# NEW_LINE_EN.net
KiCad netlist of a schematic drawn in EAGLE
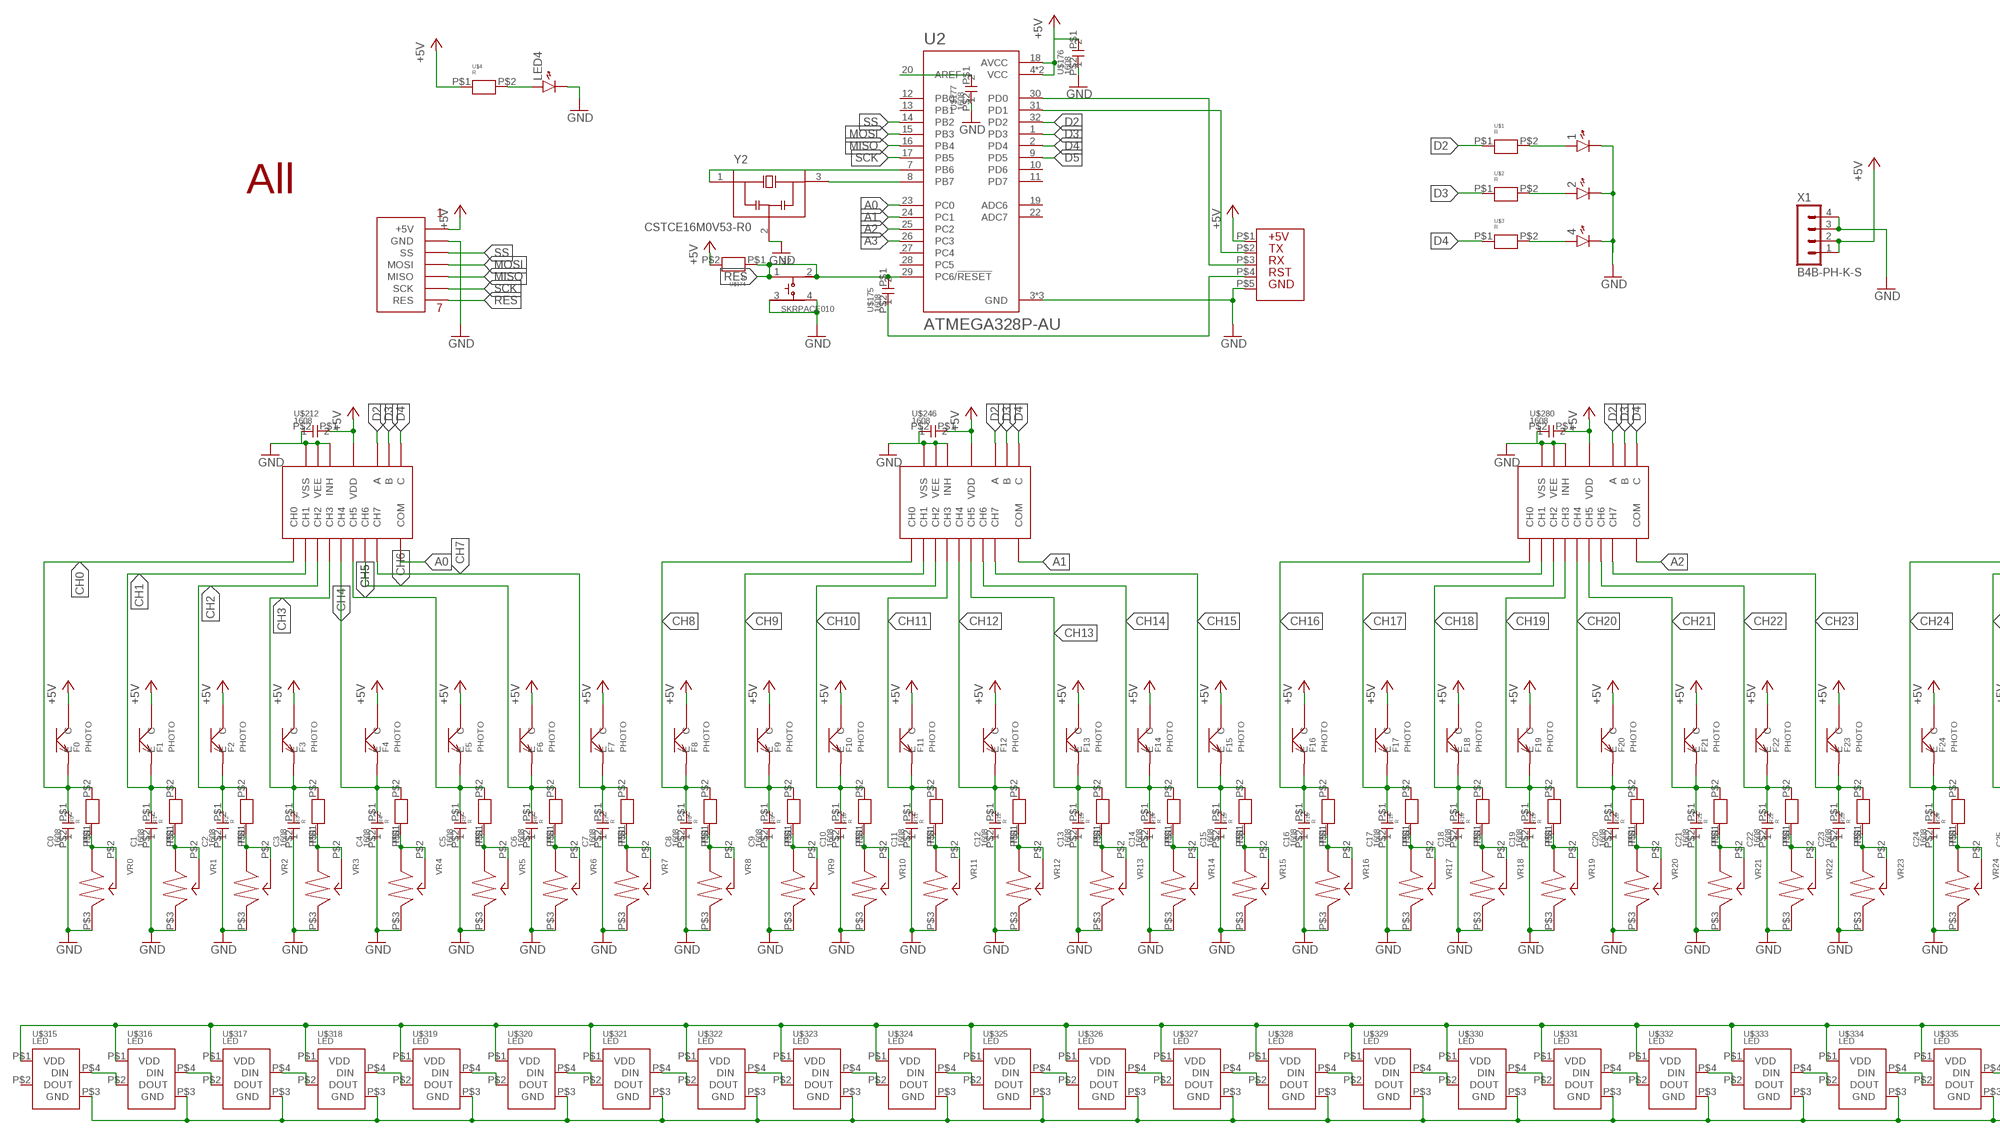
[diagram p0: schematic, sheet 1, part 1 of 2]
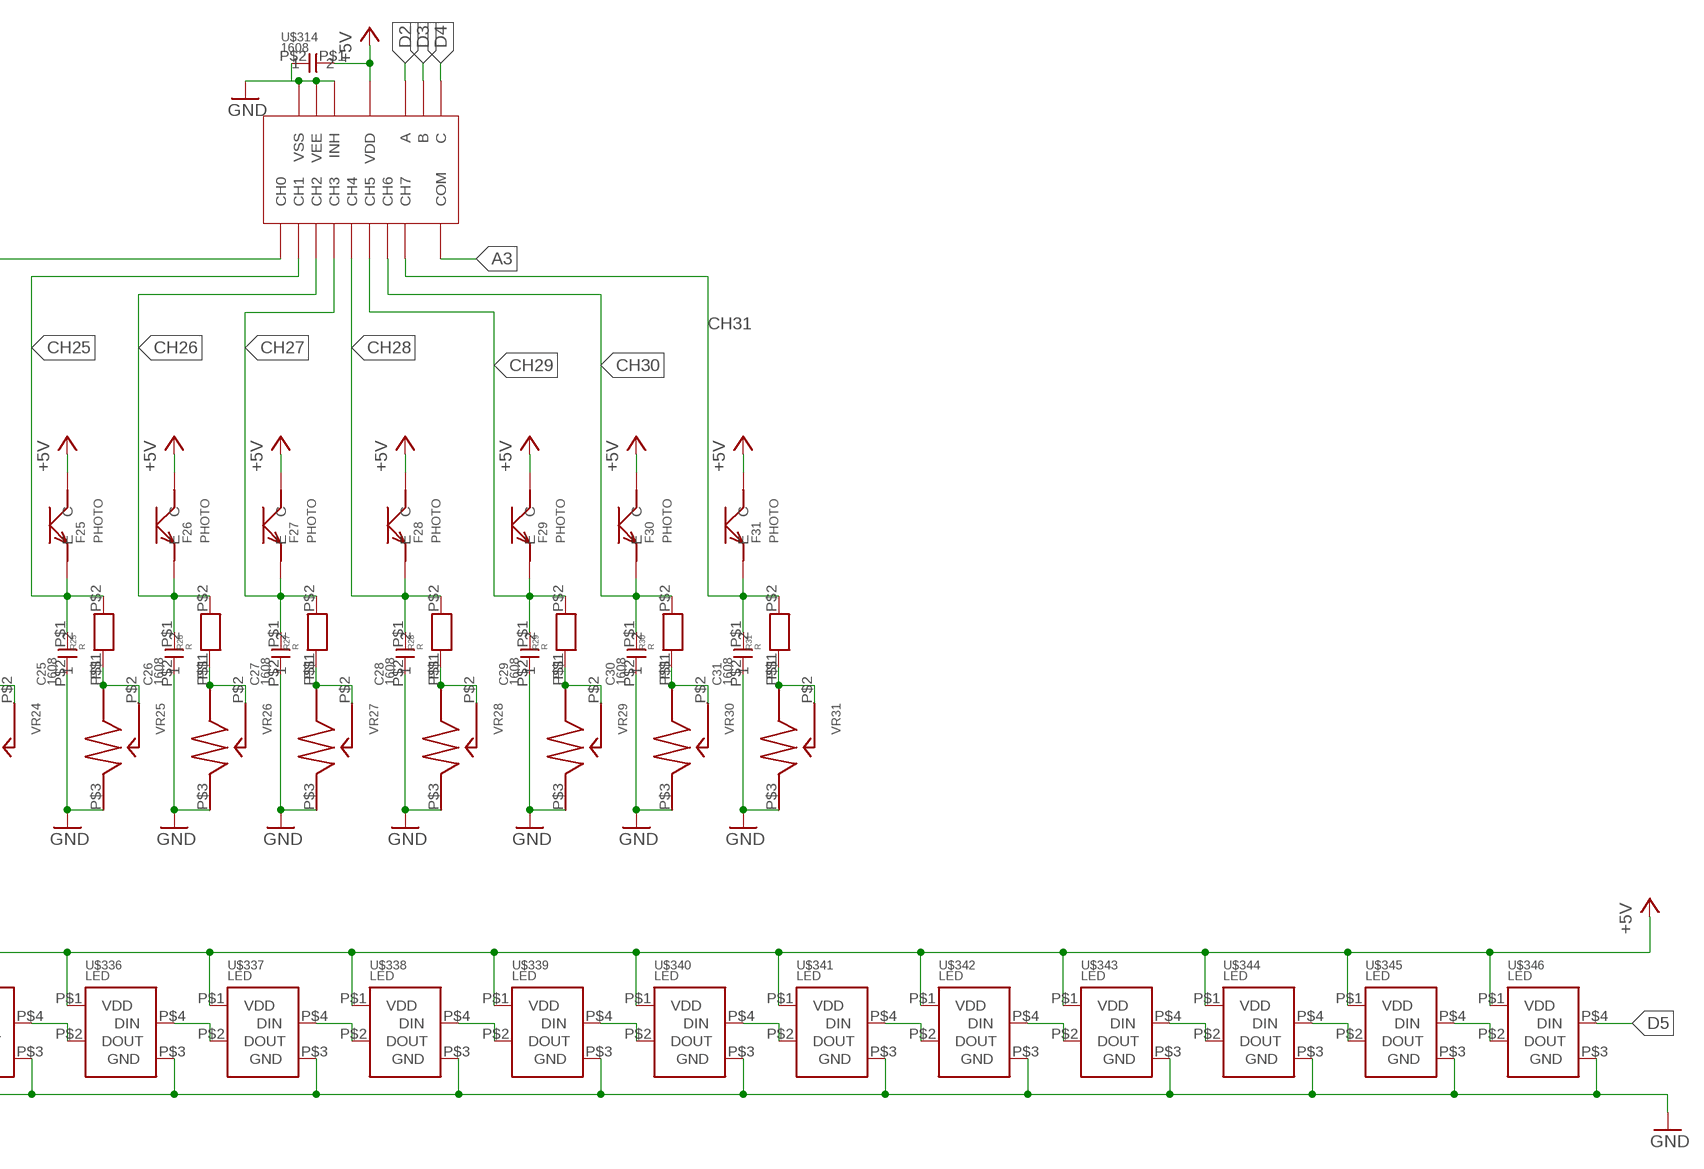
[diagram p1: schematic, sheet 1, part 2 of 2]

(export (version "E")
  (design (tool "Eeschema 10.0.6"))
  (components
    (comp (ref "1")
      (value "LED1608")
      (footprint "eagle-import:LED1608")
      (libsource (lib "eagle-import") (part "LED1608"))
    )
    (comp (ref "2")
      (value "LED1608")
      (footprint "eagle-import:LED1608")
      (libsource (lib "eagle-import") (part "LED1608"))
    )
    (comp (ref "4")
      (value "LED1608")
      (footprint "eagle-import:LED1608")
      (libsource (lib "eagle-import") (part "LED1608"))
    )
    (comp (ref "C0")
      (value "1608")
      (footprint "eagle-import:CON")
      (libsource (lib "eagle-import") (part "1608"))
    )
    (comp (ref "C1")
      (value "1608")
      (footprint "eagle-import:CON")
      (libsource (lib "eagle-import") (part "1608"))
    )
    (comp (ref "C2")
      (value "1608")
      (footprint "eagle-import:CON")
      (libsource (lib "eagle-import") (part "1608"))
    )
    (comp (ref "C3")
      (value "1608")
      (footprint "eagle-import:CON")
      (libsource (lib "eagle-import") (part "1608"))
    )
    (comp (ref "C4")
      (value "1608")
      (footprint "eagle-import:CON")
      (libsource (lib "eagle-import") (part "1608"))
    )
    (comp (ref "C5")
      (value "1608")
      (footprint "eagle-import:CON")
      (libsource (lib "eagle-import") (part "1608"))
    )
    (comp (ref "C6")
      (value "1608")
      (footprint "eagle-import:CON")
      (libsource (lib "eagle-import") (part "1608"))
    )
    (comp (ref "C7")
      (value "1608")
      (footprint "eagle-import:CON")
      (libsource (lib "eagle-import") (part "1608"))
    )
    (comp (ref "C8")
      (value "1608")
      (footprint "eagle-import:CON")
      (libsource (lib "eagle-import") (part "1608"))
    )
    (comp (ref "C9")
      (value "1608")
      (footprint "eagle-import:CON")
      (libsource (lib "eagle-import") (part "1608"))
    )
    (comp (ref "C10")
      (value "1608")
      (footprint "eagle-import:CON")
      (libsource (lib "eagle-import") (part "1608"))
    )
    (comp (ref "C11")
      (value "1608")
      (footprint "eagle-import:CON")
      (libsource (lib "eagle-import") (part "1608"))
    )
    (comp (ref "C12")
      (value "1608")
      (footprint "eagle-import:CON")
      (libsource (lib "eagle-import") (part "1608"))
    )
    (comp (ref "C13")
      (value "1608")
      (footprint "eagle-import:CON")
      (libsource (lib "eagle-import") (part "1608"))
    )
    (comp (ref "C14")
      (value "1608")
      (footprint "eagle-import:CON")
      (libsource (lib "eagle-import") (part "1608"))
    )
    (comp (ref "C15")
      (value "1608")
      (footprint "eagle-import:CON")
      (libsource (lib "eagle-import") (part "1608"))
    )
    (comp (ref "C16")
      (value "1608")
      (footprint "eagle-import:CON")
      (libsource (lib "eagle-import") (part "1608"))
    )
    (comp (ref "C17")
      (value "1608")
      (footprint "eagle-import:CON")
      (libsource (lib "eagle-import") (part "1608"))
    )
    (comp (ref "C18")
      (value "1608")
      (footprint "eagle-import:CON")
      (libsource (lib "eagle-import") (part "1608"))
    )
    (comp (ref "C19")
      (value "1608")
      (footprint "eagle-import:CON")
      (libsource (lib "eagle-import") (part "1608"))
    )
    (comp (ref "C20")
      (value "1608")
      (footprint "eagle-import:CON")
      (libsource (lib "eagle-import") (part "1608"))
    )
    (comp (ref "C21")
      (value "1608")
      (footprint "eagle-import:CON")
      (libsource (lib "eagle-import") (part "1608"))
    )
    (comp (ref "C22")
      (value "1608")
      (footprint "eagle-import:CON")
      (libsource (lib "eagle-import") (part "1608"))
    )
    (comp (ref "C23")
      (value "1608")
      (footprint "eagle-import:CON")
      (libsource (lib "eagle-import") (part "1608"))
    )
    (comp (ref "C24")
      (value "1608")
      (footprint "eagle-import:CON")
      (libsource (lib "eagle-import") (part "1608"))
    )
    (comp (ref "C25")
      (value "1608")
      (footprint "eagle-import:CON")
      (libsource (lib "eagle-import") (part "1608"))
    )
    (comp (ref "C26")
      (value "1608")
      (footprint "eagle-import:CON")
      (libsource (lib "eagle-import") (part "1608"))
    )
    (comp (ref "C27")
      (value "1608")
      (footprint "eagle-import:CON")
      (libsource (lib "eagle-import") (part "1608"))
    )
    (comp (ref "C28")
      (value "1608")
      (footprint "eagle-import:CON")
      (libsource (lib "eagle-import") (part "1608"))
    )
    (comp (ref "C29")
      (value "1608")
      (footprint "eagle-import:CON")
      (libsource (lib "eagle-import") (part "1608"))
    )
    (comp (ref "C30")
      (value "1608")
      (footprint "eagle-import:CON")
      (libsource (lib "eagle-import") (part "1608"))
    )
    (comp (ref "C31")
      (value "1608")
      (footprint "eagle-import:CON")
      (libsource (lib "eagle-import") (part "1608"))
    )
    (comp (ref "F0")
      (value "PHOTO")
      (footprint "eagle-import:PHOTO")
      (libsource (lib "eagle-import") (part "PHOTO"))
    )
    (comp (ref "F1")
      (value "PHOTO")
      (footprint "eagle-import:PHOTO")
      (libsource (lib "eagle-import") (part "PHOTO"))
    )
    (comp (ref "F2")
      (value "PHOTO")
      (footprint "eagle-import:PHOTO")
      (libsource (lib "eagle-import") (part "PHOTO"))
    )
    (comp (ref "F3")
      (value "PHOTO")
      (footprint "eagle-import:PHOTO")
      (libsource (lib "eagle-import") (part "PHOTO"))
    )
    (comp (ref "F4")
      (value "PHOTO")
      (footprint "eagle-import:PHOTO")
      (libsource (lib "eagle-import") (part "PHOTO"))
    )
    (comp (ref "F5")
      (value "PHOTO")
      (footprint "eagle-import:PHOTO")
      (libsource (lib "eagle-import") (part "PHOTO"))
    )
    (comp (ref "F6")
      (value "PHOTO")
      (footprint "eagle-import:PHOTO")
      (libsource (lib "eagle-import") (part "PHOTO"))
    )
    (comp (ref "F7")
      (value "PHOTO")
      (footprint "eagle-import:PHOTO")
      (libsource (lib "eagle-import") (part "PHOTO"))
    )
    (comp (ref "F8")
      (value "PHOTO")
      (footprint "eagle-import:PHOTO")
      (libsource (lib "eagle-import") (part "PHOTO"))
    )
    (comp (ref "F9")
      (value "PHOTO")
      (footprint "eagle-import:PHOTO")
      (libsource (lib "eagle-import") (part "PHOTO"))
    )
    (comp (ref "F10")
      (value "PHOTO")
      (footprint "eagle-import:PHOTO")
      (libsource (lib "eagle-import") (part "PHOTO"))
    )
    (comp (ref "F11")
      (value "PHOTO")
      (footprint "eagle-import:PHOTO")
      (libsource (lib "eagle-import") (part "PHOTO"))
    )
    (comp (ref "F12")
      (value "PHOTO")
      (footprint "eagle-import:PHOTO")
      (libsource (lib "eagle-import") (part "PHOTO"))
    )
    (comp (ref "F13")
      (value "PHOTO")
      (footprint "eagle-import:PHOTO")
      (libsource (lib "eagle-import") (part "PHOTO"))
    )
    (comp (ref "F14")
      (value "PHOTO")
      (footprint "eagle-import:PHOTO")
      (libsource (lib "eagle-import") (part "PHOTO"))
    )
    (comp (ref "F15")
      (value "PHOTO")
      (footprint "eagle-import:PHOTO")
      (libsource (lib "eagle-import") (part "PHOTO"))
    )
    (comp (ref "F16")
      (value "PHOTO")
      (footprint "eagle-import:PHOTO")
      (libsource (lib "eagle-import") (part "PHOTO"))
    )
    (comp (ref "F17")
      (value "PHOTO")
      (footprint "eagle-import:PHOTO")
      (libsource (lib "eagle-import") (part "PHOTO"))
    )
    (comp (ref "F18")
      (value "PHOTO")
      (footprint "eagle-import:PHOTO")
      (libsource (lib "eagle-import") (part "PHOTO"))
    )
    (comp (ref "F19")
      (value "PHOTO")
      (footprint "eagle-import:PHOTO")
      (libsource (lib "eagle-import") (part "PHOTO"))
    )
    (comp (ref "F20")
      (value "PHOTO")
      (footprint "eagle-import:PHOTO")
      (libsource (lib "eagle-import") (part "PHOTO"))
    )
    (comp (ref "F21")
      (value "PHOTO")
      (footprint "eagle-import:PHOTO")
      (libsource (lib "eagle-import") (part "PHOTO"))
    )
    (comp (ref "F22")
      (value "PHOTO")
      (footprint "eagle-import:PHOTO")
      (libsource (lib "eagle-import") (part "PHOTO"))
    )
    (comp (ref "F23")
      (value "PHOTO")
      (footprint "eagle-import:PHOTO")
      (libsource (lib "eagle-import") (part "PHOTO"))
    )
    (comp (ref "F24")
      (value "PHOTO")
      (footprint "eagle-import:PHOTO")
      (libsource (lib "eagle-import") (part "PHOTO"))
    )
    (comp (ref "F25")
      (value "PHOTO")
      (footprint "eagle-import:PHOTO")
      (libsource (lib "eagle-import") (part "PHOTO"))
    )
    (comp (ref "F26")
      (value "PHOTO")
      (footprint "eagle-import:PHOTO")
      (libsource (lib "eagle-import") (part "PHOTO"))
    )
    (comp (ref "F27")
      (value "PHOTO")
      (footprint "eagle-import:PHOTO")
      (libsource (lib "eagle-import") (part "PHOTO"))
    )
    (comp (ref "F28")
      (value "PHOTO")
      (footprint "eagle-import:PHOTO")
      (libsource (lib "eagle-import") (part "PHOTO"))
    )
    (comp (ref "F29")
      (value "PHOTO")
      (footprint "eagle-import:PHOTO")
      (libsource (lib "eagle-import") (part "PHOTO"))
    )
    (comp (ref "F30")
      (value "PHOTO")
      (footprint "eagle-import:PHOTO")
      (libsource (lib "eagle-import") (part "PHOTO"))
    )
    (comp (ref "F31")
      (value "PHOTO")
      (footprint "eagle-import:PHOTO")
      (libsource (lib "eagle-import") (part "PHOTO"))
    )
    (comp (ref "LED4")
      (value "LED1608")
      (footprint "eagle-import:LED1608")
      (libsource (lib "eagle-import") (part "LED1608"))
    )
    (comp (ref "R0") (value "R") (footprint "eagle-import:1608") (libsource (lib "eagle-import") (part "R")))
    (comp (ref "R1") (value "R") (footprint "eagle-import:1608") (libsource (lib "eagle-import") (part "R")))
    (comp (ref "R2") (value "R") (footprint "eagle-import:1608") (libsource (lib "eagle-import") (part "R")))
    (comp (ref "R3") (value "R") (footprint "eagle-import:1608") (libsource (lib "eagle-import") (part "R")))
    (comp (ref "R4") (value "R") (footprint "eagle-import:1608") (libsource (lib "eagle-import") (part "R")))
    (comp (ref "R5") (value "R") (footprint "eagle-import:1608") (libsource (lib "eagle-import") (part "R")))
    (comp (ref "R6") (value "R") (footprint "eagle-import:1608") (libsource (lib "eagle-import") (part "R")))
    (comp (ref "R7") (value "R") (footprint "eagle-import:1608") (libsource (lib "eagle-import") (part "R")))
    (comp (ref "R8") (value "R") (footprint "eagle-import:1608") (libsource (lib "eagle-import") (part "R")))
    (comp (ref "R9") (value "R") (footprint "eagle-import:1608") (libsource (lib "eagle-import") (part "R")))
    (comp (ref "R10") (value "R") (footprint "eagle-import:1608") (libsource (lib "eagle-import") (part "R")))
    (comp (ref "R11") (value "R") (footprint "eagle-import:1608") (libsource (lib "eagle-import") (part "R")))
    (comp (ref "R12") (value "R") (footprint "eagle-import:1608") (libsource (lib "eagle-import") (part "R")))
    (comp (ref "R13") (value "R") (footprint "eagle-import:1608") (libsource (lib "eagle-import") (part "R")))
    (comp (ref "R14") (value "R") (footprint "eagle-import:1608") (libsource (lib "eagle-import") (part "R")))
    (comp (ref "R15") (value "R") (footprint "eagle-import:1608") (libsource (lib "eagle-import") (part "R")))
    (comp (ref "R16") (value "R") (footprint "eagle-import:1608") (libsource (lib "eagle-import") (part "R")))
    (comp (ref "R17") (value "R") (footprint "eagle-import:1608") (libsource (lib "eagle-import") (part "R")))
    (comp (ref "R18") (value "R") (footprint "eagle-import:1608") (libsource (lib "eagle-import") (part "R")))
    (comp (ref "R19") (value "R") (footprint "eagle-import:1608") (libsource (lib "eagle-import") (part "R")))
    (comp (ref "R20") (value "R") (footprint "eagle-import:1608") (libsource (lib "eagle-import") (part "R")))
    (comp (ref "R21") (value "R") (footprint "eagle-import:1608") (libsource (lib "eagle-import") (part "R")))
    (comp (ref "R22") (value "R") (footprint "eagle-import:1608") (libsource (lib "eagle-import") (part "R")))
    (comp (ref "R23") (value "R") (footprint "eagle-import:1608") (libsource (lib "eagle-import") (part "R")))
    (comp (ref "R24") (value "R") (footprint "eagle-import:1608") (libsource (lib "eagle-import") (part "R")))
    (comp (ref "R25") (value "R") (footprint "eagle-import:1608") (libsource (lib "eagle-import") (part "R")))
    (comp (ref "R26") (value "R") (footprint "eagle-import:1608") (libsource (lib "eagle-import") (part "R")))
    (comp (ref "R27") (value "R") (footprint "eagle-import:1608") (libsource (lib "eagle-import") (part "R")))
    (comp (ref "R28") (value "R") (footprint "eagle-import:1608") (libsource (lib "eagle-import") (part "R")))
    (comp (ref "R29") (value "R") (footprint "eagle-import:1608") (libsource (lib "eagle-import") (part "R")))
    (comp (ref "R30") (value "R") (footprint "eagle-import:1608") (libsource (lib "eagle-import") (part "R")))
    (comp (ref "R31") (value "R") (footprint "eagle-import:1608") (libsource (lib "eagle-import") (part "R")))
    (comp (ref "S2")
      (value "SKRPACE010")
      (footprint "eagle-import:SW_SKRPACE010")
      (fields (field (name "MF") "ALPS"))
      (libsource (lib "eagle-import") (part "SKRPACE010"))
    )
    (comp (ref "U$1") (value "R") (footprint "eagle-import:1608") (libsource (lib "eagle-import") (part "R")))
    (comp (ref "U$2") (value "R") (footprint "eagle-import:1608") (libsource (lib "eagle-import") (part "R")))
    (comp (ref "U$3") (value "R") (footprint "eagle-import:1608") (libsource (lib "eagle-import") (part "R")))
    (comp (ref "U$4") (value "R") (footprint "eagle-import:1608") (libsource (lib "eagle-import") (part "R")))
    (comp (ref "U$5")
      (value "SPI")
      (footprint "eagle-import:SPI")
      (libsource (lib "eagle-import") (part "SPI"))
    )
    (comp (ref "U$6") (value "SI") (footprint "eagle-import:SI") (libsource (lib "eagle-import") (part "SI")))
    (comp (ref "U$7")
      (value "ALL")
      (footprint "eagle-import:ALL")
      (libsource (lib "eagle-import") (part "ALL"))
    )
    (comp (ref "U$174")
      (value "R")
      (footprint "eagle-import:1608")
      (libsource (lib "eagle-import") (part "R"))
    )
    (comp (ref "U$175")
      (value "1608")
      (footprint "eagle-import:CON")
      (libsource (lib "eagle-import") (part "1608"))
    )
    (comp (ref "U$176")
      (value "1608")
      (footprint "eagle-import:CON")
      (libsource (lib "eagle-import") (part "1608"))
    )
    (comp (ref "U$177")
      (value "1608")
      (footprint "eagle-import:CON")
      (libsource (lib "eagle-import") (part "1608"))
    )
    (comp (ref "U$179")
      (value "AM")
      (footprint "eagle-import:SOP65P640X120-16N")
      (libsource (lib "eagle-import") (part "AM"))
    )
    (comp (ref "U$212")
      (value "1608")
      (footprint "eagle-import:CON")
      (libsource (lib "eagle-import") (part "1608"))
    )
    (comp (ref "U$213")
      (value "AM")
      (footprint "eagle-import:SOP65P640X120-16N")
      (libsource (lib "eagle-import") (part "AM"))
    )
    (comp (ref "U$246")
      (value "1608")
      (footprint "eagle-import:CON")
      (libsource (lib "eagle-import") (part "1608"))
    )
    (comp (ref "U$247")
      (value "AM")
      (footprint "eagle-import:SOP65P640X120-16N")
      (libsource (lib "eagle-import") (part "AM"))
    )
    (comp (ref "U$280")
      (value "1608")
      (footprint "eagle-import:CON")
      (libsource (lib "eagle-import") (part "1608"))
    )
    (comp (ref "U$281")
      (value "AM")
      (footprint "eagle-import:SOP65P640X120-16N")
      (libsource (lib "eagle-import") (part "AM"))
    )
    (comp (ref "U$314")
      (value "1608")
      (footprint "eagle-import:CON")
      (libsource (lib "eagle-import") (part "1608"))
    )
    (comp (ref "U$315")
      (value "LED")
      (footprint "eagle-import:LED")
      (libsource (lib "eagle-import") (part "LED"))
    )
    (comp (ref "U$316")
      (value "LED")
      (footprint "eagle-import:LED")
      (libsource (lib "eagle-import") (part "LED"))
    )
    (comp (ref "U$317")
      (value "LED")
      (footprint "eagle-import:LED")
      (libsource (lib "eagle-import") (part "LED"))
    )
    (comp (ref "U$318")
      (value "LED")
      (footprint "eagle-import:LED")
      (libsource (lib "eagle-import") (part "LED"))
    )
    (comp (ref "U$319")
      (value "LED")
      (footprint "eagle-import:LED")
      (libsource (lib "eagle-import") (part "LED"))
    )
    (comp (ref "U$320")
      (value "LED")
      (footprint "eagle-import:LED")
      (libsource (lib "eagle-import") (part "LED"))
    )
    (comp (ref "U$321")
      (value "LED")
      (footprint "eagle-import:LED")
      (libsource (lib "eagle-import") (part "LED"))
    )
    (comp (ref "U$322")
      (value "LED")
      (footprint "eagle-import:LED")
      (libsource (lib "eagle-import") (part "LED"))
    )
    (comp (ref "U$323")
      (value "LED")
      (footprint "eagle-import:LED")
      (libsource (lib "eagle-import") (part "LED"))
    )
    (comp (ref "U$324")
      (value "LED")
      (footprint "eagle-import:LED")
      (libsource (lib "eagle-import") (part "LED"))
    )
    (comp (ref "U$325")
      (value "LED")
      (footprint "eagle-import:LED")
      (libsource (lib "eagle-import") (part "LED"))
    )
    (comp (ref "U$326")
      (value "LED")
      (footprint "eagle-import:LED")
      (libsource (lib "eagle-import") (part "LED"))
    )
    (comp (ref "U$327")
      (value "LED")
      (footprint "eagle-import:LED")
      (libsource (lib "eagle-import") (part "LED"))
    )
    (comp (ref "U$328")
      (value "LED")
      (footprint "eagle-import:LED")
      (libsource (lib "eagle-import") (part "LED"))
    )
    (comp (ref "U$329")
      (value "LED")
      (footprint "eagle-import:LED")
      (libsource (lib "eagle-import") (part "LED"))
    )
    (comp (ref "U$330")
      (value "LED")
      (footprint "eagle-import:LED")
      (libsource (lib "eagle-import") (part "LED"))
    )
    (comp (ref "U$331")
      (value "LED")
      (footprint "eagle-import:LED")
      (libsource (lib "eagle-import") (part "LED"))
    )
    (comp (ref "U$332")
      (value "LED")
      (footprint "eagle-import:LED")
      (libsource (lib "eagle-import") (part "LED"))
    )
    (comp (ref "U$333")
      (value "LED")
      (footprint "eagle-import:LED")
      (libsource (lib "eagle-import") (part "LED"))
    )
    (comp (ref "U$334")
      (value "LED")
      (footprint "eagle-import:LED")
      (libsource (lib "eagle-import") (part "LED"))
    )
    (comp (ref "U$335")
      (value "LED")
      (footprint "eagle-import:LED")
      (libsource (lib "eagle-import") (part "LED"))
    )
    (comp (ref "U$336")
      (value "LED")
      (footprint "eagle-import:LED")
      (libsource (lib "eagle-import") (part "LED"))
    )
    (comp (ref "U$337")
      (value "LED")
      (footprint "eagle-import:LED")
      (libsource (lib "eagle-import") (part "LED"))
    )
    (comp (ref "U$338")
      (value "LED")
      (footprint "eagle-import:LED")
      (libsource (lib "eagle-import") (part "LED"))
    )
    (comp (ref "U$339")
      (value "LED")
      (footprint "eagle-import:LED")
      (libsource (lib "eagle-import") (part "LED"))
    )
    (comp (ref "U$340")
      (value "LED")
      (footprint "eagle-import:LED")
      (libsource (lib "eagle-import") (part "LED"))
    )
    (comp (ref "U$341")
      (value "LED")
      (footprint "eagle-import:LED")
      (libsource (lib "eagle-import") (part "LED"))
    )
    (comp (ref "U$342")
      (value "LED")
      (footprint "eagle-import:LED")
      (libsource (lib "eagle-import") (part "LED"))
    )
    (comp (ref "U$343")
      (value "LED")
      (footprint "eagle-import:LED")
      (libsource (lib "eagle-import") (part "LED"))
    )
    (comp (ref "U$344")
      (value "LED")
      (footprint "eagle-import:LED")
      (libsource (lib "eagle-import") (part "LED"))
    )
    (comp (ref "U$345")
      (value "LED")
      (footprint "eagle-import:LED")
      (libsource (lib "eagle-import") (part "LED"))
    )
    (comp (ref "U$346")
      (value "LED")
      (footprint "eagle-import:LED")
      (libsource (lib "eagle-import") (part "LED"))
    )
    (comp (ref "U2")
      (value "ATMEGA328P-AU")
      (footprint "eagle-import:QFP80P900X900X120-32N")
      (fields (field (name "MF") "Microchip Technology"))
      (libsource (lib "eagle-import") (part "ATMEGA328P-AU"))
    )
    (comp (ref "VR0") (value "VR") (footprint "eagle-import:VR") (libsource (lib "eagle-import") (part "VR")))
    (comp (ref "VR1") (value "VR") (footprint "eagle-import:VR") (libsource (lib "eagle-import") (part "VR")))
    (comp (ref "VR2") (value "VR") (footprint "eagle-import:VR") (libsource (lib "eagle-import") (part "VR")))
    (comp (ref "VR3") (value "VR") (footprint "eagle-import:VR") (libsource (lib "eagle-import") (part "VR")))
    (comp (ref "VR4") (value "VR") (footprint "eagle-import:VR") (libsource (lib "eagle-import") (part "VR")))
    (comp (ref "VR5") (value "VR") (footprint "eagle-import:VR") (libsource (lib "eagle-import") (part "VR")))
    (comp (ref "VR6") (value "VR") (footprint "eagle-import:VR") (libsource (lib "eagle-import") (part "VR")))
    (comp (ref "VR7") (value "VR") (footprint "eagle-import:VR") (libsource (lib "eagle-import") (part "VR")))
    (comp (ref "VR8") (value "VR") (footprint "eagle-import:VR") (libsource (lib "eagle-import") (part "VR")))
    (comp (ref "VR9") (value "VR") (footprint "eagle-import:VR") (libsource (lib "eagle-import") (part "VR")))
    (comp (ref "VR10")
      (value "VR")
      (footprint "eagle-import:VR")
      (libsource (lib "eagle-import") (part "VR"))
    )
    (comp (ref "VR11")
      (value "VR")
      (footprint "eagle-import:VR")
      (libsource (lib "eagle-import") (part "VR"))
    )
    (comp (ref "VR12")
      (value "VR")
      (footprint "eagle-import:VR")
      (libsource (lib "eagle-import") (part "VR"))
    )
    (comp (ref "VR13")
      (value "VR")
      (footprint "eagle-import:VR")
      (libsource (lib "eagle-import") (part "VR"))
    )
    (comp (ref "VR14")
      (value "VR")
      (footprint "eagle-import:VR")
      (libsource (lib "eagle-import") (part "VR"))
    )
    (comp (ref "VR15")
      (value "VR")
      (footprint "eagle-import:VR")
      (libsource (lib "eagle-import") (part "VR"))
    )
    (comp (ref "VR16")
      (value "VR")
      (footprint "eagle-import:VR")
      (libsource (lib "eagle-import") (part "VR"))
    )
    (comp (ref "VR17")
      (value "VR")
      (footprint "eagle-import:VR")
      (libsource (lib "eagle-import") (part "VR"))
    )
    (comp (ref "VR18")
      (value "VR")
      (footprint "eagle-import:VR")
      (libsource (lib "eagle-import") (part "VR"))
    )
    (comp (ref "VR19")
      (value "VR")
      (footprint "eagle-import:VR")
      (libsource (lib "eagle-import") (part "VR"))
    )
    (comp (ref "VR20")
      (value "VR")
      (footprint "eagle-import:VR")
      (libsource (lib "eagle-import") (part "VR"))
    )
    (comp (ref "VR21")
      (value "VR")
      (footprint "eagle-import:VR")
      (libsource (lib "eagle-import") (part "VR"))
    )
    (comp (ref "VR22")
      (value "VR")
      (footprint "eagle-import:VR")
      (libsource (lib "eagle-import") (part "VR"))
    )
    (comp (ref "VR23")
      (value "VR")
      (footprint "eagle-import:VR")
      (libsource (lib "eagle-import") (part "VR"))
    )
    (comp (ref "VR24")
      (value "VR")
      (footprint "eagle-import:VR")
      (libsource (lib "eagle-import") (part "VR"))
    )
    (comp (ref "VR25")
      (value "VR")
      (footprint "eagle-import:VR")
      (libsource (lib "eagle-import") (part "VR"))
    )
    (comp (ref "VR26")
      (value "VR")
      (footprint "eagle-import:VR")
      (libsource (lib "eagle-import") (part "VR"))
    )
    (comp (ref "VR27")
      (value "VR")
      (footprint "eagle-import:VR")
      (libsource (lib "eagle-import") (part "VR"))
    )
    (comp (ref "VR28")
      (value "VR")
      (footprint "eagle-import:VR")
      (libsource (lib "eagle-import") (part "VR"))
    )
    (comp (ref "VR29")
      (value "VR")
      (footprint "eagle-import:VR")
      (libsource (lib "eagle-import") (part "VR"))
    )
    (comp (ref "VR30")
      (value "VR")
      (footprint "eagle-import:VR")
      (libsource (lib "eagle-import") (part "VR"))
    )
    (comp (ref "VR31")
      (value "VR")
      (footprint "eagle-import:VR")
      (libsource (lib "eagle-import") (part "VR"))
    )
    (comp (ref "X1")
      (value "B4B-PH-K-S")
      (footprint "eagle-import:B4B-PH-K-S")
      (libsource (lib "eagle-import") (part "B4B-PH-K-S"))
    )
    (comp (ref "Y2")
      (value "CSTCE16M0V53-R0")
      (footprint "eagle-import:OSC_CSTCE16M0V53-R0")
      (fields (field (name "MANUFACTURER") "Murata"))
      (libsource (lib "eagle-import") (part "CSTCE16M0V53-R0"))
    )
  )
  (nets
    (net (code "1") (name "+5V") (class "Default")
      (node (ref "F0") (pin "P$1") (pinfunction "C_P$1") (pintype "bidirectional"))
      (node (ref "F1") (pin "P$1") (pinfunction "C_P$1") (pintype "bidirectional"))
      (node (ref "F10") (pin "P$1") (pinfunction "C_P$1") (pintype "bidirectional"))
      (node (ref "F11") (pin "P$1") (pinfunction "C_P$1") (pintype "bidirectional"))
      (node (ref "F12") (pin "P$1") (pinfunction "C_P$1") (pintype "bidirectional"))
      (node (ref "F13") (pin "P$1") (pinfunction "C_P$1") (pintype "bidirectional"))
      (node (ref "F14") (pin "P$1") (pinfunction "C_P$1") (pintype "bidirectional"))
      (node (ref "F15") (pin "P$1") (pinfunction "C_P$1") (pintype "bidirectional"))
      (node (ref "F16") (pin "P$1") (pinfunction "C_P$1") (pintype "bidirectional"))
      (node (ref "F17") (pin "P$1") (pinfunction "C_P$1") (pintype "bidirectional"))
      (node (ref "F18") (pin "P$1") (pinfunction "C_P$1") (pintype "bidirectional"))
      (node (ref "F19") (pin "P$1") (pinfunction "C_P$1") (pintype "bidirectional"))
      (node (ref "F2") (pin "P$1") (pinfunction "C_P$1") (pintype "bidirectional"))
      (node (ref "F20") (pin "P$1") (pinfunction "C_P$1") (pintype "bidirectional"))
      (node (ref "F21") (pin "P$1") (pinfunction "C_P$1") (pintype "bidirectional"))
      (node (ref "F22") (pin "P$1") (pinfunction "C_P$1") (pintype "bidirectional"))
      (node (ref "F23") (pin "P$1") (pinfunction "C_P$1") (pintype "bidirectional"))
      (node (ref "F24") (pin "P$1") (pinfunction "C_P$1") (pintype "bidirectional"))
      (node (ref "F25") (pin "P$1") (pinfunction "C_P$1") (pintype "bidirectional"))
      (node (ref "F26") (pin "P$1") (pinfunction "C_P$1") (pintype "bidirectional"))
      (node (ref "F27") (pin "P$1") (pinfunction "C_P$1") (pintype "bidirectional"))
      (node (ref "F28") (pin "P$1") (pinfunction "C_P$1") (pintype "bidirectional"))
      (node (ref "F29") (pin "P$1") (pinfunction "C_P$1") (pintype "bidirectional"))
      (node (ref "F3") (pin "P$1") (pinfunction "C_P$1") (pintype "bidirectional"))
      (node (ref "F30") (pin "P$1") (pinfunction "C_P$1") (pintype "bidirectional"))
      (node (ref "F31") (pin "P$1") (pinfunction "C_P$1") (pintype "bidirectional"))
      (node (ref "F4") (pin "P$1") (pinfunction "C_P$1") (pintype "bidirectional"))
      (node (ref "F5") (pin "P$1") (pinfunction "C_P$1") (pintype "bidirectional"))
      (node (ref "F6") (pin "P$1") (pinfunction "C_P$1") (pintype "bidirectional"))
      (node (ref "F7") (pin "P$1") (pinfunction "C_P$1") (pintype "bidirectional"))
      (node (ref "F8") (pin "P$1") (pinfunction "C_P$1") (pintype "bidirectional"))
      (node (ref "F9") (pin "P$1") (pinfunction "C_P$1") (pintype "bidirectional"))
      (node (ref "U$174") (pin "P$2") (pinfunction "P$2_P$2") (pintype "bidirectional"))
      (node (ref "U$176") (pin "P$1") (pinfunction "1_P$1") (pintype "bidirectional"))
      (node (ref "U$179") (pin "16") (pinfunction "VDD_16") (pintype "bidirectional"))
      (node (ref "U$212") (pin "P$1") (pinfunction "1_P$1") (pintype "bidirectional"))
      (node (ref "U$213") (pin "16") (pinfunction "VDD_16") (pintype "bidirectional"))
      (node (ref "U$246") (pin "P$1") (pinfunction "1_P$1") (pintype "bidirectional"))
      (node (ref "U$247") (pin "16") (pinfunction "VDD_16") (pintype "bidirectional"))
      (node (ref "U$280") (pin "P$1") (pinfunction "1_P$1") (pintype "bidirectional"))
      (node (ref "U$281") (pin "16") (pinfunction "VDD_16") (pintype "bidirectional"))
      (node (ref "U$314") (pin "P$1") (pinfunction "1_P$1") (pintype "bidirectional"))
      (node (ref "U$315") (pin "P$1") (pinfunction "VDD_P$1") (pintype "bidirectional"))
      (node (ref "U$316") (pin "P$1") (pinfunction "VDD_P$1") (pintype "bidirectional"))
      (node (ref "U$317") (pin "P$1") (pinfunction "VDD_P$1") (pintype "bidirectional"))
      (node (ref "U$318") (pin "P$1") (pinfunction "VDD_P$1") (pintype "bidirectional"))
      (node (ref "U$319") (pin "P$1") (pinfunction "VDD_P$1") (pintype "bidirectional"))
      (node (ref "U$320") (pin "P$1") (pinfunction "VDD_P$1") (pintype "bidirectional"))
      (node (ref "U$321") (pin "P$1") (pinfunction "VDD_P$1") (pintype "bidirectional"))
      (node (ref "U$322") (pin "P$1") (pinfunction "VDD_P$1") (pintype "bidirectional"))
      (node (ref "U$323") (pin "P$1") (pinfunction "VDD_P$1") (pintype "bidirectional"))
      (node (ref "U$324") (pin "P$1") (pinfunction "VDD_P$1") (pintype "bidirectional"))
      (node (ref "U$325") (pin "P$1") (pinfunction "VDD_P$1") (pintype "bidirectional"))
      (node (ref "U$326") (pin "P$1") (pinfunction "VDD_P$1") (pintype "bidirectional"))
      (node (ref "U$327") (pin "P$1") (pinfunction "VDD_P$1") (pintype "bidirectional"))
      (node (ref "U$328") (pin "P$1") (pinfunction "VDD_P$1") (pintype "bidirectional"))
      (node (ref "U$329") (pin "P$1") (pinfunction "VDD_P$1") (pintype "bidirectional"))
      (node (ref "U$330") (pin "P$1") (pinfunction "VDD_P$1") (pintype "bidirectional"))
      (node (ref "U$331") (pin "P$1") (pinfunction "VDD_P$1") (pintype "bidirectional"))
      (node (ref "U$332") (pin "P$1") (pinfunction "VDD_P$1") (pintype "bidirectional"))
      (node (ref "U$333") (pin "P$1") (pinfunction "VDD_P$1") (pintype "bidirectional"))
      (node (ref "U$334") (pin "P$1") (pinfunction "VDD_P$1") (pintype "bidirectional"))
      (node (ref "U$335") (pin "P$1") (pinfunction "VDD_P$1") (pintype "bidirectional"))
      (node (ref "U$336") (pin "P$1") (pinfunction "VDD_P$1") (pintype "bidirectional"))
      (node (ref "U$337") (pin "P$1") (pinfunction "VDD_P$1") (pintype "bidirectional"))
      (node (ref "U$338") (pin "P$1") (pinfunction "VDD_P$1") (pintype "bidirectional"))
      (node (ref "U$339") (pin "P$1") (pinfunction "VDD_P$1") (pintype "bidirectional"))
      (node (ref "U$340") (pin "P$1") (pinfunction "VDD_P$1") (pintype "bidirectional"))
      (node (ref "U$341") (pin "P$1") (pinfunction "VDD_P$1") (pintype "bidirectional"))
      (node (ref "U$342") (pin "P$1") (pinfunction "VDD_P$1") (pintype "bidirectional"))
      (node (ref "U$343") (pin "P$1") (pinfunction "VDD_P$1") (pintype "bidirectional"))
      (node (ref "U$344") (pin "P$1") (pinfunction "VDD_P$1") (pintype "bidirectional"))
      (node (ref "U$345") (pin "P$1") (pinfunction "VDD_P$1") (pintype "bidirectional"))
      (node (ref "U$346") (pin "P$1") (pinfunction "VDD_P$1") (pintype "bidirectional"))
      (node (ref "U$4") (pin "P$1") (pinfunction "P$1_P$1") (pintype "bidirectional"))
      (node (ref "U$5") (pin "P$1") (pinfunction "+5V_P$1") (pintype "bidirectional"))
      (node (ref "U$6") (pin "P$1") (pinfunction "P$1_P$1") (pintype "bidirectional"))
      (node (ref "U2") (pin "18") (pinfunction "AVCC_18") (pintype "power_in"))
      (node (ref "U2") (pin "4") (pinfunction "VCC_4") (pintype "power_in"))
      (node (ref "U2") (pin "6") (pinfunction "VCC_6") (pintype "power_in"))
      (node (ref "X1") (pin "1") (pinfunction "1_1") (pintype "passive"))
      (node (ref "X1") (pin "2") (pinfunction "2_2") (pintype "passive"))
    )
    (net (code "2") (name "A0") (class "Default")
      (node (ref "U$179") (pin "3") (pinfunction "COM_3") (pintype "bidirectional"))
      (node (ref "U2") (pin "23") (pinfunction "PC0_23") (pintype "bidirectional"))
    )
    (net (code "3") (name "A1") (class "Default")
      (node (ref "U$213") (pin "3") (pinfunction "COM_3") (pintype "bidirectional"))
      (node (ref "U2") (pin "24") (pinfunction "PC1_24") (pintype "bidirectional"))
    )
    (net (code "4") (name "A2") (class "Default")
      (node (ref "U$247") (pin "3") (pinfunction "COM_3") (pintype "bidirectional"))
      (node (ref "U2") (pin "25") (pinfunction "PC2_25") (pintype "bidirectional"))
    )
    (net (code "5") (name "A3") (class "Default")
      (node (ref "U$281") (pin "3") (pinfunction "COM_3") (pintype "bidirectional"))
      (node (ref "U2") (pin "26") (pinfunction "PC3_26") (pintype "bidirectional"))
    )
    (net (code "6") (name "CH0") (class "Default")
      (node (ref "C0") (pin "P$1") (pinfunction "1_P$1") (pintype "bidirectional"))
      (node (ref "F0") (pin "P$2") (pinfunction "E_P$2") (pintype "bidirectional"))
      (node (ref "R0") (pin "P$2") (pinfunction "P$2_P$2") (pintype "bidirectional"))
      (node (ref "U$179") (pin "13") (pinfunction "CH0_13") (pintype "bidirectional"))
    )
    (net (code "7") (name "CH1") (class "Default")
      (node (ref "C1") (pin "P$1") (pinfunction "1_P$1") (pintype "bidirectional"))
      (node (ref "F1") (pin "P$2") (pinfunction "E_P$2") (pintype "bidirectional"))
      (node (ref "R1") (pin "P$2") (pinfunction "P$2_P$2") (pintype "bidirectional"))
      (node (ref "U$179") (pin "14") (pinfunction "CH1_14") (pintype "bidirectional"))
    )
    (net (code "8") (name "CH2") (class "Default")
      (node (ref "C2") (pin "P$1") (pinfunction "1_P$1") (pintype "bidirectional"))
      (node (ref "F2") (pin "P$2") (pinfunction "E_P$2") (pintype "bidirectional"))
      (node (ref "R2") (pin "P$2") (pinfunction "P$2_P$2") (pintype "bidirectional"))
      (node (ref "U$179") (pin "15") (pinfunction "CH2_15") (pintype "bidirectional"))
    )
    (net (code "9") (name "CH3") (class "Default")
      (node (ref "C3") (pin "P$1") (pinfunction "1_P$1") (pintype "bidirectional"))
      (node (ref "F3") (pin "P$2") (pinfunction "E_P$2") (pintype "bidirectional"))
      (node (ref "R3") (pin "P$2") (pinfunction "P$2_P$2") (pintype "bidirectional"))
      (node (ref "U$179") (pin "12") (pinfunction "CH3_12") (pintype "bidirectional"))
    )
    (net (code "10") (name "CH4") (class "Default")
      (node (ref "C4") (pin "P$1") (pinfunction "1_P$1") (pintype "bidirectional"))
      (node (ref "F4") (pin "P$2") (pinfunction "E_P$2") (pintype "bidirectional"))
      (node (ref "R4") (pin "P$2") (pinfunction "P$2_P$2") (pintype "bidirectional"))
      (node (ref "U$179") (pin "1") (pinfunction "CH4_1") (pintype "bidirectional"))
    )
    (net (code "11") (name "CH5") (class "Default")
      (node (ref "C5") (pin "P$1") (pinfunction "1_P$1") (pintype "bidirectional"))
      (node (ref "F5") (pin "P$2") (pinfunction "E_P$2") (pintype "bidirectional"))
      (node (ref "R5") (pin "P$2") (pinfunction "P$2_P$2") (pintype "bidirectional"))
      (node (ref "U$179") (pin "5") (pinfunction "CH5_5") (pintype "bidirectional"))
    )
    (net (code "12") (name "CH6") (class "Default")
      (node (ref "C6") (pin "P$1") (pinfunction "1_P$1") (pintype "bidirectional"))
      (node (ref "F6") (pin "P$2") (pinfunction "E_P$2") (pintype "bidirectional"))
      (node (ref "R6") (pin "P$2") (pinfunction "P$2_P$2") (pintype "bidirectional"))
      (node (ref "U$179") (pin "2") (pinfunction "CH6_2") (pintype "bidirectional"))
    )
    (net (code "13") (name "CH7") (class "Default")
      (node (ref "C7") (pin "P$1") (pinfunction "1_P$1") (pintype "bidirectional"))
      (node (ref "F7") (pin "P$2") (pinfunction "E_P$2") (pintype "bidirectional"))
      (node (ref "R7") (pin "P$2") (pinfunction "P$2_P$2") (pintype "bidirectional"))
      (node (ref "U$179") (pin "4") (pinfunction "CH7_4") (pintype "bidirectional"))
    )
    (net (code "14") (name "CH8") (class "Default")
      (node (ref "C8") (pin "P$1") (pinfunction "1_P$1") (pintype "bidirectional"))
      (node (ref "F8") (pin "P$2") (pinfunction "E_P$2") (pintype "bidirectional"))
      (node (ref "R8") (pin "P$2") (pinfunction "P$2_P$2") (pintype "bidirectional"))
      (node (ref "U$213") (pin "13") (pinfunction "CH0_13") (pintype "bidirectional"))
    )
    (net (code "15") (name "CH9") (class "Default")
      (node (ref "C9") (pin "P$1") (pinfunction "1_P$1") (pintype "bidirectional"))
      (node (ref "F9") (pin "P$2") (pinfunction "E_P$2") (pintype "bidirectional"))
      (node (ref "R9") (pin "P$2") (pinfunction "P$2_P$2") (pintype "bidirectional"))
      (node (ref "U$213") (pin "14") (pinfunction "CH1_14") (pintype "bidirectional"))
    )
    (net (code "16") (name "CH10") (class "Default")
      (node (ref "C10") (pin "P$1") (pinfunction "1_P$1") (pintype "bidirectional"))
      (node (ref "F10") (pin "P$2") (pinfunction "E_P$2") (pintype "bidirectional"))
      (node (ref "R10") (pin "P$2") (pinfunction "P$2_P$2") (pintype "bidirectional"))
      (node (ref "U$213") (pin "15") (pinfunction "CH2_15") (pintype "bidirectional"))
    )
    (net (code "17") (name "CH11") (class "Default")
      (node (ref "C11") (pin "P$1") (pinfunction "1_P$1") (pintype "bidirectional"))
      (node (ref "F11") (pin "P$2") (pinfunction "E_P$2") (pintype "bidirectional"))
      (node (ref "R11") (pin "P$2") (pinfunction "P$2_P$2") (pintype "bidirectional"))
      (node (ref "U$213") (pin "12") (pinfunction "CH3_12") (pintype "bidirectional"))
    )
    (net (code "18") (name "CH12") (class "Default")
      (node (ref "C12") (pin "P$1") (pinfunction "1_P$1") (pintype "bidirectional"))
      (node (ref "F12") (pin "P$2") (pinfunction "E_P$2") (pintype "bidirectional"))
      (node (ref "R12") (pin "P$2") (pinfunction "P$2_P$2") (pintype "bidirectional"))
      (node (ref "U$213") (pin "1") (pinfunction "CH4_1") (pintype "bidirectional"))
    )
    (net (code "19") (name "CH13") (class "Default")
      (node (ref "C13") (pin "P$1") (pinfunction "1_P$1") (pintype "bidirectional"))
      (node (ref "F13") (pin "P$2") (pinfunction "E_P$2") (pintype "bidirectional"))
      (node (ref "R13") (pin "P$2") (pinfunction "P$2_P$2") (pintype "bidirectional"))
      (node (ref "U$213") (pin "5") (pinfunction "CH5_5") (pintype "bidirectional"))
    )
    (net (code "20") (name "CH14") (class "Default")
      (node (ref "C14") (pin "P$1") (pinfunction "1_P$1") (pintype "bidirectional"))
      (node (ref "F14") (pin "P$2") (pinfunction "E_P$2") (pintype "bidirectional"))
      (node (ref "R14") (pin "P$2") (pinfunction "P$2_P$2") (pintype "bidirectional"))
      (node (ref "U$213") (pin "2") (pinfunction "CH6_2") (pintype "bidirectional"))
    )
    (net (code "21") (name "CH15") (class "Default")
      (node (ref "C15") (pin "P$1") (pinfunction "1_P$1") (pintype "bidirectional"))
      (node (ref "F15") (pin "P$2") (pinfunction "E_P$2") (pintype "bidirectional"))
      (node (ref "R15") (pin "P$2") (pinfunction "P$2_P$2") (pintype "bidirectional"))
      (node (ref "U$213") (pin "4") (pinfunction "CH7_4") (pintype "bidirectional"))
    )
    (net (code "22") (name "CH16") (class "Default")
      (node (ref "C16") (pin "P$1") (pinfunction "1_P$1") (pintype "bidirectional"))
      (node (ref "F16") (pin "P$2") (pinfunction "E_P$2") (pintype "bidirectional"))
      (node (ref "R16") (pin "P$2") (pinfunction "P$2_P$2") (pintype "bidirectional"))
      (node (ref "U$247") (pin "13") (pinfunction "CH0_13") (pintype "bidirectional"))
    )
    (net (code "23") (name "CH17") (class "Default")
      (node (ref "C17") (pin "P$1") (pinfunction "1_P$1") (pintype "bidirectional"))
      (node (ref "F17") (pin "P$2") (pinfunction "E_P$2") (pintype "bidirectional"))
      (node (ref "R17") (pin "P$2") (pinfunction "P$2_P$2") (pintype "bidirectional"))
      (node (ref "U$247") (pin "14") (pinfunction "CH1_14") (pintype "bidirectional"))
    )
    (net (code "24") (name "CH18") (class "Default")
      (node (ref "C18") (pin "P$1") (pinfunction "1_P$1") (pintype "bidirectional"))
      (node (ref "F18") (pin "P$2") (pinfunction "E_P$2") (pintype "bidirectional"))
      (node (ref "R18") (pin "P$2") (pinfunction "P$2_P$2") (pintype "bidirectional"))
      (node (ref "U$247") (pin "15") (pinfunction "CH2_15") (pintype "bidirectional"))
    )
    (net (code "25") (name "CH19") (class "Default")
      (node (ref "C19") (pin "P$1") (pinfunction "1_P$1") (pintype "bidirectional"))
      (node (ref "F19") (pin "P$2") (pinfunction "E_P$2") (pintype "bidirectional"))
      (node (ref "R19") (pin "P$2") (pinfunction "P$2_P$2") (pintype "bidirectional"))
      (node (ref "U$247") (pin "12") (pinfunction "CH3_12") (pintype "bidirectional"))
    )
    (net (code "26") (name "CH20") (class "Default")
      (node (ref "C20") (pin "P$1") (pinfunction "1_P$1") (pintype "bidirectional"))
      (node (ref "F20") (pin "P$2") (pinfunction "E_P$2") (pintype "bidirectional"))
      (node (ref "R20") (pin "P$2") (pinfunction "P$2_P$2") (pintype "bidirectional"))
      (node (ref "U$247") (pin "1") (pinfunction "CH4_1") (pintype "bidirectional"))
    )
    (net (code "27") (name "CH21") (class "Default")
      (node (ref "C21") (pin "P$1") (pinfunction "1_P$1") (pintype "bidirectional"))
      (node (ref "F21") (pin "P$2") (pinfunction "E_P$2") (pintype "bidirectional"))
      (node (ref "R21") (pin "P$2") (pinfunction "P$2_P$2") (pintype "bidirectional"))
      (node (ref "U$247") (pin "5") (pinfunction "CH5_5") (pintype "bidirectional"))
    )
    (net (code "28") (name "CH22") (class "Default")
      (node (ref "C22") (pin "P$1") (pinfunction "1_P$1") (pintype "bidirectional"))
      (node (ref "F22") (pin "P$2") (pinfunction "E_P$2") (pintype "bidirectional"))
      (node (ref "R22") (pin "P$2") (pinfunction "P$2_P$2") (pintype "bidirectional"))
      (node (ref "U$247") (pin "2") (pinfunction "CH6_2") (pintype "bidirectional"))
    )
    (net (code "29") (name "CH23") (class "Default")
      (node (ref "C23") (pin "P$1") (pinfunction "1_P$1") (pintype "bidirectional"))
      (node (ref "F23") (pin "P$2") (pinfunction "E_P$2") (pintype "bidirectional"))
      (node (ref "R23") (pin "P$2") (pinfunction "P$2_P$2") (pintype "bidirectional"))
      (node (ref "U$247") (pin "4") (pinfunction "CH7_4") (pintype "bidirectional"))
    )
    (net (code "30") (name "CH24") (class "Default")
      (node (ref "C24") (pin "P$1") (pinfunction "1_P$1") (pintype "bidirectional"))
      (node (ref "F24") (pin "P$2") (pinfunction "E_P$2") (pintype "bidirectional"))
      (node (ref "R24") (pin "P$2") (pinfunction "P$2_P$2") (pintype "bidirectional"))
      (node (ref "U$281") (pin "13") (pinfunction "CH0_13") (pintype "bidirectional"))
    )
    (net (code "31") (name "CH25") (class "Default")
      (node (ref "C25") (pin "P$1") (pinfunction "1_P$1") (pintype "bidirectional"))
      (node (ref "F25") (pin "P$2") (pinfunction "E_P$2") (pintype "bidirectional"))
      (node (ref "R25") (pin "P$2") (pinfunction "P$2_P$2") (pintype "bidirectional"))
      (node (ref "U$281") (pin "14") (pinfunction "CH1_14") (pintype "bidirectional"))
    )
    (net (code "32") (name "CH26") (class "Default")
      (node (ref "C26") (pin "P$1") (pinfunction "1_P$1") (pintype "bidirectional"))
      (node (ref "F26") (pin "P$2") (pinfunction "E_P$2") (pintype "bidirectional"))
      (node (ref "R26") (pin "P$2") (pinfunction "P$2_P$2") (pintype "bidirectional"))
      (node (ref "U$281") (pin "15") (pinfunction "CH2_15") (pintype "bidirectional"))
    )
    (net (code "33") (name "CH27") (class "Default")
      (node (ref "C27") (pin "P$1") (pinfunction "1_P$1") (pintype "bidirectional"))
      (node (ref "F27") (pin "P$2") (pinfunction "E_P$2") (pintype "bidirectional"))
      (node (ref "R27") (pin "P$2") (pinfunction "P$2_P$2") (pintype "bidirectional"))
      (node (ref "U$281") (pin "12") (pinfunction "CH3_12") (pintype "bidirectional"))
    )
    (net (code "34") (name "CH28") (class "Default")
      (node (ref "C28") (pin "P$1") (pinfunction "1_P$1") (pintype "bidirectional"))
      (node (ref "F28") (pin "P$2") (pinfunction "E_P$2") (pintype "bidirectional"))
      (node (ref "R28") (pin "P$2") (pinfunction "P$2_P$2") (pintype "bidirectional"))
      (node (ref "U$281") (pin "1") (pinfunction "CH4_1") (pintype "bidirectional"))
    )
    (net (code "35") (name "CH29") (class "Default")
      (node (ref "C29") (pin "P$1") (pinfunction "1_P$1") (pintype "bidirectional"))
      (node (ref "F29") (pin "P$2") (pinfunction "E_P$2") (pintype "bidirectional"))
      (node (ref "R29") (pin "P$2") (pinfunction "P$2_P$2") (pintype "bidirectional"))
      (node (ref "U$281") (pin "5") (pinfunction "CH5_5") (pintype "bidirectional"))
    )
    (net (code "36") (name "CH30") (class "Default")
      (node (ref "C30") (pin "P$1") (pinfunction "1_P$1") (pintype "bidirectional"))
      (node (ref "F30") (pin "P$2") (pinfunction "E_P$2") (pintype "bidirectional"))
      (node (ref "R30") (pin "P$2") (pinfunction "P$2_P$2") (pintype "bidirectional"))
      (node (ref "U$281") (pin "2") (pinfunction "CH6_2") (pintype "bidirectional"))
    )
    (net (code "37") (name "CH31") (class "Default")
      (node (ref "C31") (pin "P$1") (pinfunction "1_P$1") (pintype "bidirectional"))
      (node (ref "F31") (pin "P$2") (pinfunction "E_P$2") (pintype "bidirectional"))
      (node (ref "R31") (pin "P$2") (pinfunction "P$2_P$2") (pintype "bidirectional"))
      (node (ref "U$281") (pin "4") (pinfunction "CH7_4") (pintype "bidirectional"))
    )
    (net (code "38") (name "D2") (class "Default")
      (node (ref "U$1") (pin "P$1") (pinfunction "P$1_P$1") (pintype "bidirectional"))
      (node (ref "U$179") (pin "11") (pinfunction "A_11") (pintype "bidirectional"))
      (node (ref "U$213") (pin "11") (pinfunction "A_11") (pintype "bidirectional"))
      (node (ref "U$247") (pin "11") (pinfunction "A_11") (pintype "bidirectional"))
      (node (ref "U$281") (pin "11") (pinfunction "A_11") (pintype "bidirectional"))
      (node (ref "U2") (pin "32") (pinfunction "PD2_32") (pintype "bidirectional"))
    )
    (net (code "39") (name "D3") (class "Default")
      (node (ref "U$179") (pin "10") (pinfunction "B_10") (pintype "bidirectional"))
      (node (ref "U$2") (pin "P$1") (pinfunction "P$1_P$1") (pintype "bidirectional"))
      (node (ref "U$213") (pin "10") (pinfunction "B_10") (pintype "bidirectional"))
      (node (ref "U$247") (pin "10") (pinfunction "B_10") (pintype "bidirectional"))
      (node (ref "U$281") (pin "10") (pinfunction "B_10") (pintype "bidirectional"))
      (node (ref "U2") (pin "1") (pinfunction "PD3_1") (pintype "bidirectional"))
    )
    (net (code "40") (name "D4") (class "Default")
      (node (ref "U$179") (pin "9") (pinfunction "C_9") (pintype "bidirectional"))
      (node (ref "U$213") (pin "9") (pinfunction "C_9") (pintype "bidirectional"))
      (node (ref "U$247") (pin "9") (pinfunction "C_9") (pintype "bidirectional"))
      (node (ref "U$281") (pin "9") (pinfunction "C_9") (pintype "bidirectional"))
      (node (ref "U$3") (pin "P$1") (pinfunction "P$1_P$1") (pintype "bidirectional"))
      (node (ref "U2") (pin "2") (pinfunction "PD4_2") (pintype "bidirectional"))
    )
    (net (code "41") (name "D5") (class "Default")
      (node (ref "U$346") (pin "P$4") (pinfunction "DIN_P$4") (pintype "bidirectional"))
      (node (ref "U2") (pin "9") (pinfunction "PD5_9") (pintype "bidirectional"))
    )
    (net (code "42") (name "GND") (class "Default")
      (node (ref "1") (pin "K") (pinfunction "K_K") (pintype "passive"))
      (node (ref "2") (pin "K") (pinfunction "K_K") (pintype "passive"))
      (node (ref "4") (pin "K") (pinfunction "K_K") (pintype "passive"))
      (node (ref "C0") (pin "P$2") (pinfunction "2_P$2") (pintype "bidirectional"))
      (node (ref "C1") (pin "P$2") (pinfunction "2_P$2") (pintype "bidirectional"))
      (node (ref "C10") (pin "P$2") (pinfunction "2_P$2") (pintype "bidirectional"))
      (node (ref "C11") (pin "P$2") (pinfunction "2_P$2") (pintype "bidirectional"))
      (node (ref "C12") (pin "P$2") (pinfunction "2_P$2") (pintype "bidirectional"))
      (node (ref "C13") (pin "P$2") (pinfunction "2_P$2") (pintype "bidirectional"))
      (node (ref "C14") (pin "P$2") (pinfunction "2_P$2") (pintype "bidirectional"))
      (node (ref "C15") (pin "P$2") (pinfunction "2_P$2") (pintype "bidirectional"))
      (node (ref "C16") (pin "P$2") (pinfunction "2_P$2") (pintype "bidirectional"))
      (node (ref "C17") (pin "P$2") (pinfunction "2_P$2") (pintype "bidirectional"))
      (node (ref "C18") (pin "P$2") (pinfunction "2_P$2") (pintype "bidirectional"))
      (node (ref "C19") (pin "P$2") (pinfunction "2_P$2") (pintype "bidirectional"))
      (node (ref "C2") (pin "P$2") (pinfunction "2_P$2") (pintype "bidirectional"))
      (node (ref "C20") (pin "P$2") (pinfunction "2_P$2") (pintype "bidirectional"))
      (node (ref "C21") (pin "P$2") (pinfunction "2_P$2") (pintype "bidirectional"))
      (node (ref "C22") (pin "P$2") (pinfunction "2_P$2") (pintype "bidirectional"))
      (node (ref "C23") (pin "P$2") (pinfunction "2_P$2") (pintype "bidirectional"))
      (node (ref "C24") (pin "P$2") (pinfunction "2_P$2") (pintype "bidirectional"))
      (node (ref "C25") (pin "P$2") (pinfunction "2_P$2") (pintype "bidirectional"))
      (node (ref "C26") (pin "P$2") (pinfunction "2_P$2") (pintype "bidirectional"))
      (node (ref "C27") (pin "P$2") (pinfunction "2_P$2") (pintype "bidirectional"))
      (node (ref "C28") (pin "P$2") (pinfunction "2_P$2") (pintype "bidirectional"))
      (node (ref "C29") (pin "P$2") (pinfunction "2_P$2") (pintype "bidirectional"))
      (node (ref "C3") (pin "P$2") (pinfunction "2_P$2") (pintype "bidirectional"))
      (node (ref "C30") (pin "P$2") (pinfunction "2_P$2") (pintype "bidirectional"))
      (node (ref "C31") (pin "P$2") (pinfunction "2_P$2") (pintype "bidirectional"))
      (node (ref "C4") (pin "P$2") (pinfunction "2_P$2") (pintype "bidirectional"))
      (node (ref "C5") (pin "P$2") (pinfunction "2_P$2") (pintype "bidirectional"))
      (node (ref "C6") (pin "P$2") (pinfunction "2_P$2") (pintype "bidirectional"))
      (node (ref "C7") (pin "P$2") (pinfunction "2_P$2") (pintype "bidirectional"))
      (node (ref "C8") (pin "P$2") (pinfunction "2_P$2") (pintype "bidirectional"))
      (node (ref "C9") (pin "P$2") (pinfunction "2_P$2") (pintype "bidirectional"))
      (node (ref "LED4") (pin "K") (pinfunction "K_K") (pintype "passive"))
      (node (ref "S2") (pin "3") (pinfunction "3_3") (pintype "bidirectional"))
      (node (ref "S2") (pin "4") (pinfunction "4_4") (pintype "bidirectional"))
      (node (ref "U$176") (pin "P$2") (pinfunction "2_P$2") (pintype "bidirectional"))
      (node (ref "U$177") (pin "P$2") (pinfunction "2_P$2") (pintype "bidirectional"))
      (node (ref "U$179") (pin "6") (pinfunction "INH_6") (pintype "bidirectional"))
      (node (ref "U$179") (pin "7") (pinfunction "VEE_7") (pintype "bidirectional"))
      (node (ref "U$179") (pin "8") (pinfunction "VSS_8") (pintype "bidirectional"))
      (node (ref "U$212") (pin "P$2") (pinfunction "2_P$2") (pintype "bidirectional"))
      (node (ref "U$213") (pin "6") (pinfunction "INH_6") (pintype "bidirectional"))
      (node (ref "U$213") (pin "7") (pinfunction "VEE_7") (pintype "bidirectional"))
      (node (ref "U$213") (pin "8") (pinfunction "VSS_8") (pintype "bidirectional"))
      (node (ref "U$246") (pin "P$2") (pinfunction "2_P$2") (pintype "bidirectional"))
      (node (ref "U$247") (pin "6") (pinfunction "INH_6") (pintype "bidirectional"))
      (node (ref "U$247") (pin "7") (pinfunction "VEE_7") (pintype "bidirectional"))
      (node (ref "U$247") (pin "8") (pinfunction "VSS_8") (pintype "bidirectional"))
      (node (ref "U$280") (pin "P$2") (pinfunction "2_P$2") (pintype "bidirectional"))
      (node (ref "U$281") (pin "6") (pinfunction "INH_6") (pintype "bidirectional"))
      (node (ref "U$281") (pin "7") (pinfunction "VEE_7") (pintype "bidirectional"))
      (node (ref "U$281") (pin "8") (pinfunction "VSS_8") (pintype "bidirectional"))
      (node (ref "U$314") (pin "P$2") (pinfunction "2_P$2") (pintype "bidirectional"))
      (node (ref "U$315") (pin "P$3") (pinfunction "GND_P$3") (pintype "bidirectional"))
      (node (ref "U$316") (pin "P$3") (pinfunction "GND_P$3") (pintype "bidirectional"))
      (node (ref "U$317") (pin "P$3") (pinfunction "GND_P$3") (pintype "bidirectional"))
      (node (ref "U$318") (pin "P$3") (pinfunction "GND_P$3") (pintype "bidirectional"))
      (node (ref "U$319") (pin "P$3") (pinfunction "GND_P$3") (pintype "bidirectional"))
      (node (ref "U$320") (pin "P$3") (pinfunction "GND_P$3") (pintype "bidirectional"))
      (node (ref "U$321") (pin "P$3") (pinfunction "GND_P$3") (pintype "bidirectional"))
      (node (ref "U$322") (pin "P$3") (pinfunction "GND_P$3") (pintype "bidirectional"))
      (node (ref "U$323") (pin "P$3") (pinfunction "GND_P$3") (pintype "bidirectional"))
      (node (ref "U$324") (pin "P$3") (pinfunction "GND_P$3") (pintype "bidirectional"))
      (node (ref "U$325") (pin "P$3") (pinfunction "GND_P$3") (pintype "bidirectional"))
      (node (ref "U$326") (pin "P$3") (pinfunction "GND_P$3") (pintype "bidirectional"))
      (node (ref "U$327") (pin "P$3") (pinfunction "GND_P$3") (pintype "bidirectional"))
      (node (ref "U$328") (pin "P$3") (pinfunction "GND_P$3") (pintype "bidirectional"))
      (node (ref "U$329") (pin "P$3") (pinfunction "GND_P$3") (pintype "bidirectional"))
      (node (ref "U$330") (pin "P$3") (pinfunction "GND_P$3") (pintype "bidirectional"))
      (node (ref "U$331") (pin "P$3") (pinfunction "GND_P$3") (pintype "bidirectional"))
      (node (ref "U$332") (pin "P$3") (pinfunction "GND_P$3") (pintype "bidirectional"))
      (node (ref "U$333") (pin "P$3") (pinfunction "GND_P$3") (pintype "bidirectional"))
      (node (ref "U$334") (pin "P$3") (pinfunction "GND_P$3") (pintype "bidirectional"))
      (node (ref "U$335") (pin "P$3") (pinfunction "GND_P$3") (pintype "bidirectional"))
      (node (ref "U$336") (pin "P$3") (pinfunction "GND_P$3") (pintype "bidirectional"))
      (node (ref "U$337") (pin "P$3") (pinfunction "GND_P$3") (pintype "bidirectional"))
      (node (ref "U$338") (pin "P$3") (pinfunction "GND_P$3") (pintype "bidirectional"))
      (node (ref "U$339") (pin "P$3") (pinfunction "GND_P$3") (pintype "bidirectional"))
      (node (ref "U$340") (pin "P$3") (pinfunction "GND_P$3") (pintype "bidirectional"))
      (node (ref "U$341") (pin "P$3") (pinfunction "GND_P$3") (pintype "bidirectional"))
      (node (ref "U$342") (pin "P$3") (pinfunction "GND_P$3") (pintype "bidirectional"))
      (node (ref "U$343") (pin "P$3") (pinfunction "GND_P$3") (pintype "bidirectional"))
      (node (ref "U$344") (pin "P$3") (pinfunction "GND_P$3") (pintype "bidirectional"))
      (node (ref "U$345") (pin "P$3") (pinfunction "GND_P$3") (pintype "bidirectional"))
      (node (ref "U$346") (pin "P$3") (pinfunction "GND_P$3") (pintype "bidirectional"))
      (node (ref "U$5") (pin "P$2") (pinfunction "GND_P$2") (pintype "bidirectional"))
      (node (ref "U$6") (pin "P$5") (pinfunction "P$5_P$5") (pintype "bidirectional"))
      (node (ref "U2") (pin "21") (pinfunction "GND_21") (pintype "power_in"))
      (node (ref "U2") (pin "3") (pinfunction "GND_3") (pintype "power_in"))
      (node (ref "U2") (pin "5") (pinfunction "GND_5") (pintype "power_in"))
      (node (ref "VR0") (pin "P$3") (pinfunction "P$3_P$3") (pintype "bidirectional"))
      (node (ref "VR1") (pin "P$3") (pinfunction "P$3_P$3") (pintype "bidirectional"))
      (node (ref "VR10") (pin "P$3") (pinfunction "P$3_P$3") (pintype "bidirectional"))
      (node (ref "VR11") (pin "P$3") (pinfunction "P$3_P$3") (pintype "bidirectional"))
      (node (ref "VR12") (pin "P$3") (pinfunction "P$3_P$3") (pintype "bidirectional"))
      (node (ref "VR13") (pin "P$3") (pinfunction "P$3_P$3") (pintype "bidirectional"))
      (node (ref "VR14") (pin "P$3") (pinfunction "P$3_P$3") (pintype "bidirectional"))
      (node (ref "VR15") (pin "P$3") (pinfunction "P$3_P$3") (pintype "bidirectional"))
      (node (ref "VR16") (pin "P$3") (pinfunction "P$3_P$3") (pintype "bidirectional"))
      (node (ref "VR17") (pin "P$3") (pinfunction "P$3_P$3") (pintype "bidirectional"))
      (node (ref "VR18") (pin "P$3") (pinfunction "P$3_P$3") (pintype "bidirectional"))
      (node (ref "VR19") (pin "P$3") (pinfunction "P$3_P$3") (pintype "bidirectional"))
      (node (ref "VR2") (pin "P$3") (pinfunction "P$3_P$3") (pintype "bidirectional"))
      (node (ref "VR20") (pin "P$3") (pinfunction "P$3_P$3") (pintype "bidirectional"))
      (node (ref "VR21") (pin "P$3") (pinfunction "P$3_P$3") (pintype "bidirectional"))
      (node (ref "VR22") (pin "P$3") (pinfunction "P$3_P$3") (pintype "bidirectional"))
      (node (ref "VR23") (pin "P$3") (pinfunction "P$3_P$3") (pintype "bidirectional"))
      (node (ref "VR24") (pin "P$3") (pinfunction "P$3_P$3") (pintype "bidirectional"))
      (node (ref "VR25") (pin "P$3") (pinfunction "P$3_P$3") (pintype "bidirectional"))
      (node (ref "VR26") (pin "P$3") (pinfunction "P$3_P$3") (pintype "bidirectional"))
      (node (ref "VR27") (pin "P$3") (pinfunction "P$3_P$3") (pintype "bidirectional"))
      (node (ref "VR28") (pin "P$3") (pinfunction "P$3_P$3") (pintype "bidirectional"))
      (node (ref "VR29") (pin "P$3") (pinfunction "P$3_P$3") (pintype "bidirectional"))
      (node (ref "VR3") (pin "P$3") (pinfunction "P$3_P$3") (pintype "bidirectional"))
      (node (ref "VR30") (pin "P$3") (pinfunction "P$3_P$3") (pintype "bidirectional"))
      (node (ref "VR31") (pin "P$3") (pinfunction "P$3_P$3") (pintype "bidirectional"))
      (node (ref "VR4") (pin "P$3") (pinfunction "P$3_P$3") (pintype "bidirectional"))
      (node (ref "VR5") (pin "P$3") (pinfunction "P$3_P$3") (pintype "bidirectional"))
      (node (ref "VR6") (pin "P$3") (pinfunction "P$3_P$3") (pintype "bidirectional"))
      (node (ref "VR7") (pin "P$3") (pinfunction "P$3_P$3") (pintype "bidirectional"))
      (node (ref "VR8") (pin "P$3") (pinfunction "P$3_P$3") (pintype "bidirectional"))
      (node (ref "VR9") (pin "P$3") (pinfunction "P$3_P$3") (pintype "bidirectional"))
      (node (ref "X1") (pin "3") (pinfunction "3_3") (pintype "passive"))
      (node (ref "X1") (pin "4") (pinfunction "4_4") (pintype "passive"))
      (node (ref "Y2") (pin "2") (pinfunction "GND_2") (pintype "power_in"))
    )
    (net (code "43") (name "MISO") (class "Default")
      (node (ref "U$5") (pin "P$5") (pinfunction "MISO_P$5") (pintype "bidirectional"))
      (node (ref "U2") (pin "16") (pinfunction "PB4_16") (pintype "bidirectional"))
    )
    (net (code "44") (name "MOSI") (class "Default")
      (node (ref "U$5") (pin "P$4") (pinfunction "MOSI_P$4") (pintype "bidirectional"))
      (node (ref "U2") (pin "15") (pinfunction "PB3_15") (pintype "bidirectional"))
    )
    (net (code "45") (name "Net-(1-PadA)") (class "Default")
      (node (ref "1") (pin "A") (pinfunction "A_A") (pintype "passive"))
      (node (ref "U$1") (pin "P$2") (pinfunction "P$2_P$2") (pintype "bidirectional"))
    )
    (net (code "46") (name "Net-(2-PadA)") (class "Default")
      (node (ref "2") (pin "A") (pinfunction "A_A") (pintype "passive"))
      (node (ref "U$2") (pin "P$2") (pinfunction "P$2_P$2") (pintype "bidirectional"))
    )
    (net (code "47") (name "Net-(4-PadA)") (class "Default")
      (node (ref "4") (pin "A") (pinfunction "A_A") (pintype "passive"))
      (node (ref "U$3") (pin "P$2") (pinfunction "P$2_P$2") (pintype "bidirectional"))
    )
    (net (code "48") (name "Net-(LED4-PadA)") (class "Default")
      (node (ref "LED4") (pin "A") (pinfunction "A_A") (pintype "passive"))
      (node (ref "U$4") (pin "P$2") (pinfunction "P$2_P$2") (pintype "bidirectional"))
    )
    (net (code "49") (name "Net-(R0-PadP$1)") (class "Default")
      (node (ref "R0") (pin "P$1") (pinfunction "P$1_P$1") (pintype "bidirectional"))
      (node (ref "VR0") (pin "P$1") (pinfunction "P$1_P$1") (pintype "bidirectional"))
      (node (ref "VR0") (pin "P$2") (pinfunction "P$2_P$2") (pintype "bidirectional"))
    )
    (net (code "50") (name "Net-(R1-PadP$1)") (class "Default")
      (node (ref "R1") (pin "P$1") (pinfunction "P$1_P$1") (pintype "bidirectional"))
      (node (ref "VR1") (pin "P$1") (pinfunction "P$1_P$1") (pintype "bidirectional"))
      (node (ref "VR1") (pin "P$2") (pinfunction "P$2_P$2") (pintype "bidirectional"))
    )
    (net (code "51") (name "Net-(R2-PadP$1)") (class "Default")
      (node (ref "R2") (pin "P$1") (pinfunction "P$1_P$1") (pintype "bidirectional"))
      (node (ref "VR2") (pin "P$1") (pinfunction "P$1_P$1") (pintype "bidirectional"))
      (node (ref "VR2") (pin "P$2") (pinfunction "P$2_P$2") (pintype "bidirectional"))
    )
    (net (code "52") (name "Net-(R3-PadP$1)") (class "Default")
      (node (ref "R3") (pin "P$1") (pinfunction "P$1_P$1") (pintype "bidirectional"))
      (node (ref "VR3") (pin "P$1") (pinfunction "P$1_P$1") (pintype "bidirectional"))
      (node (ref "VR3") (pin "P$2") (pinfunction "P$2_P$2") (pintype "bidirectional"))
    )
    (net (code "53") (name "Net-(R4-PadP$1)") (class "Default")
      (node (ref "R4") (pin "P$1") (pinfunction "P$1_P$1") (pintype "bidirectional"))
      (node (ref "VR4") (pin "P$1") (pinfunction "P$1_P$1") (pintype "bidirectional"))
      (node (ref "VR4") (pin "P$2") (pinfunction "P$2_P$2") (pintype "bidirectional"))
    )
    (net (code "54") (name "Net-(R5-PadP$1)") (class "Default")
      (node (ref "R5") (pin "P$1") (pinfunction "P$1_P$1") (pintype "bidirectional"))
      (node (ref "VR5") (pin "P$1") (pinfunction "P$1_P$1") (pintype "bidirectional"))
      (node (ref "VR5") (pin "P$2") (pinfunction "P$2_P$2") (pintype "bidirectional"))
    )
    (net (code "55") (name "Net-(R6-PadP$1)") (class "Default")
      (node (ref "R6") (pin "P$1") (pinfunction "P$1_P$1") (pintype "bidirectional"))
      (node (ref "VR6") (pin "P$1") (pinfunction "P$1_P$1") (pintype "bidirectional"))
      (node (ref "VR6") (pin "P$2") (pinfunction "P$2_P$2") (pintype "bidirectional"))
    )
    (net (code "56") (name "Net-(R7-PadP$1)") (class "Default")
      (node (ref "R7") (pin "P$1") (pinfunction "P$1_P$1") (pintype "bidirectional"))
      (node (ref "VR7") (pin "P$1") (pinfunction "P$1_P$1") (pintype "bidirectional"))
      (node (ref "VR7") (pin "P$2") (pinfunction "P$2_P$2") (pintype "bidirectional"))
    )
    (net (code "57") (name "Net-(R8-PadP$1)") (class "Default")
      (node (ref "R8") (pin "P$1") (pinfunction "P$1_P$1") (pintype "bidirectional"))
      (node (ref "VR8") (pin "P$1") (pinfunction "P$1_P$1") (pintype "bidirectional"))
      (node (ref "VR8") (pin "P$2") (pinfunction "P$2_P$2") (pintype "bidirectional"))
    )
    (net (code "58") (name "Net-(R9-PadP$1)") (class "Default")
      (node (ref "R9") (pin "P$1") (pinfunction "P$1_P$1") (pintype "bidirectional"))
      (node (ref "VR9") (pin "P$1") (pinfunction "P$1_P$1") (pintype "bidirectional"))
      (node (ref "VR9") (pin "P$2") (pinfunction "P$2_P$2") (pintype "bidirectional"))
    )
    (net (code "59") (name "Net-(R10-PadP$1)") (class "Default")
      (node (ref "R10") (pin "P$1") (pinfunction "P$1_P$1") (pintype "bidirectional"))
      (node (ref "VR10") (pin "P$1") (pinfunction "P$1_P$1") (pintype "bidirectional"))
      (node (ref "VR10") (pin "P$2") (pinfunction "P$2_P$2") (pintype "bidirectional"))
    )
    (net (code "60") (name "Net-(R11-PadP$1)") (class "Default")
      (node (ref "R11") (pin "P$1") (pinfunction "P$1_P$1") (pintype "bidirectional"))
      (node (ref "VR11") (pin "P$1") (pinfunction "P$1_P$1") (pintype "bidirectional"))
      (node (ref "VR11") (pin "P$2") (pinfunction "P$2_P$2") (pintype "bidirectional"))
    )
    (net (code "61") (name "Net-(R12-PadP$1)") (class "Default")
      (node (ref "R12") (pin "P$1") (pinfunction "P$1_P$1") (pintype "bidirectional"))
      (node (ref "VR12") (pin "P$1") (pinfunction "P$1_P$1") (pintype "bidirectional"))
      (node (ref "VR12") (pin "P$2") (pinfunction "P$2_P$2") (pintype "bidirectional"))
    )
    (net (code "62") (name "Net-(R13-PadP$1)") (class "Default")
      (node (ref "R13") (pin "P$1") (pinfunction "P$1_P$1") (pintype "bidirectional"))
      (node (ref "VR13") (pin "P$1") (pinfunction "P$1_P$1") (pintype "bidirectional"))
      (node (ref "VR13") (pin "P$2") (pinfunction "P$2_P$2") (pintype "bidirectional"))
    )
    (net (code "63") (name "Net-(R14-PadP$1)") (class "Default")
      (node (ref "R14") (pin "P$1") (pinfunction "P$1_P$1") (pintype "bidirectional"))
      (node (ref "VR14") (pin "P$1") (pinfunction "P$1_P$1") (pintype "bidirectional"))
      (node (ref "VR14") (pin "P$2") (pinfunction "P$2_P$2") (pintype "bidirectional"))
    )
    (net (code "64") (name "Net-(R15-PadP$1)") (class "Default")
      (node (ref "R15") (pin "P$1") (pinfunction "P$1_P$1") (pintype "bidirectional"))
      (node (ref "VR15") (pin "P$1") (pinfunction "P$1_P$1") (pintype "bidirectional"))
      (node (ref "VR15") (pin "P$2") (pinfunction "P$2_P$2") (pintype "bidirectional"))
    )
    (net (code "65") (name "Net-(R16-PadP$1)") (class "Default")
      (node (ref "R16") (pin "P$1") (pinfunction "P$1_P$1") (pintype "bidirectional"))
      (node (ref "VR16") (pin "P$1") (pinfunction "P$1_P$1") (pintype "bidirectional"))
      (node (ref "VR16") (pin "P$2") (pinfunction "P$2_P$2") (pintype "bidirectional"))
    )
    (net (code "66") (name "Net-(R17-PadP$1)") (class "Default")
      (node (ref "R17") (pin "P$1") (pinfunction "P$1_P$1") (pintype "bidirectional"))
      (node (ref "VR17") (pin "P$1") (pinfunction "P$1_P$1") (pintype "bidirectional"))
      (node (ref "VR17") (pin "P$2") (pinfunction "P$2_P$2") (pintype "bidirectional"))
    )
    (net (code "67") (name "Net-(R18-PadP$1)") (class "Default")
      (node (ref "R18") (pin "P$1") (pinfunction "P$1_P$1") (pintype "bidirectional"))
      (node (ref "VR18") (pin "P$1") (pinfunction "P$1_P$1") (pintype "bidirectional"))
      (node (ref "VR18") (pin "P$2") (pinfunction "P$2_P$2") (pintype "bidirectional"))
    )
    (net (code "68") (name "Net-(R19-PadP$1)") (class "Default")
      (node (ref "R19") (pin "P$1") (pinfunction "P$1_P$1") (pintype "bidirectional"))
      (node (ref "VR19") (pin "P$1") (pinfunction "P$1_P$1") (pintype "bidirectional"))
      (node (ref "VR19") (pin "P$2") (pinfunction "P$2_P$2") (pintype "bidirectional"))
    )
    (net (code "69") (name "Net-(R20-PadP$1)") (class "Default")
      (node (ref "R20") (pin "P$1") (pinfunction "P$1_P$1") (pintype "bidirectional"))
      (node (ref "VR20") (pin "P$1") (pinfunction "P$1_P$1") (pintype "bidirectional"))
      (node (ref "VR20") (pin "P$2") (pinfunction "P$2_P$2") (pintype "bidirectional"))
    )
    (net (code "70") (name "Net-(R21-PadP$1)") (class "Default")
      (node (ref "R21") (pin "P$1") (pinfunction "P$1_P$1") (pintype "bidirectional"))
      (node (ref "VR21") (pin "P$1") (pinfunction "P$1_P$1") (pintype "bidirectional"))
      (node (ref "VR21") (pin "P$2") (pinfunction "P$2_P$2") (pintype "bidirectional"))
    )
    (net (code "71") (name "Net-(R22-PadP$1)") (class "Default")
      (node (ref "R22") (pin "P$1") (pinfunction "P$1_P$1") (pintype "bidirectional"))
      (node (ref "VR22") (pin "P$1") (pinfunction "P$1_P$1") (pintype "bidirectional"))
      (node (ref "VR22") (pin "P$2") (pinfunction "P$2_P$2") (pintype "bidirectional"))
    )
    (net (code "72") (name "Net-(R23-PadP$1)") (class "Default")
      (node (ref "R23") (pin "P$1") (pinfunction "P$1_P$1") (pintype "bidirectional"))
      (node (ref "VR23") (pin "P$1") (pinfunction "P$1_P$1") (pintype "bidirectional"))
      (node (ref "VR23") (pin "P$2") (pinfunction "P$2_P$2") (pintype "bidirectional"))
    )
    (net (code "73") (name "Net-(R24-PadP$1)") (class "Default")
      (node (ref "R24") (pin "P$1") (pinfunction "P$1_P$1") (pintype "bidirectional"))
      (node (ref "VR24") (pin "P$1") (pinfunction "P$1_P$1") (pintype "bidirectional"))
      (node (ref "VR24") (pin "P$2") (pinfunction "P$2_P$2") (pintype "bidirectional"))
    )
    (net (code "74") (name "Net-(R25-PadP$1)") (class "Default")
      (node (ref "R25") (pin "P$1") (pinfunction "P$1_P$1") (pintype "bidirectional"))
      (node (ref "VR25") (pin "P$1") (pinfunction "P$1_P$1") (pintype "bidirectional"))
      (node (ref "VR25") (pin "P$2") (pinfunction "P$2_P$2") (pintype "bidirectional"))
    )
    (net (code "75") (name "Net-(R26-PadP$1)") (class "Default")
      (node (ref "R26") (pin "P$1") (pinfunction "P$1_P$1") (pintype "bidirectional"))
      (node (ref "VR26") (pin "P$1") (pinfunction "P$1_P$1") (pintype "bidirectional"))
      (node (ref "VR26") (pin "P$2") (pinfunction "P$2_P$2") (pintype "bidirectional"))
    )
    (net (code "76") (name "Net-(R27-PadP$1)") (class "Default")
      (node (ref "R27") (pin "P$1") (pinfunction "P$1_P$1") (pintype "bidirectional"))
      (node (ref "VR27") (pin "P$1") (pinfunction "P$1_P$1") (pintype "bidirectional"))
      (node (ref "VR27") (pin "P$2") (pinfunction "P$2_P$2") (pintype "bidirectional"))
    )
    (net (code "77") (name "Net-(R28-PadP$1)") (class "Default")
      (node (ref "R28") (pin "P$1") (pinfunction "P$1_P$1") (pintype "bidirectional"))
      (node (ref "VR28") (pin "P$1") (pinfunction "P$1_P$1") (pintype "bidirectional"))
      (node (ref "VR28") (pin "P$2") (pinfunction "P$2_P$2") (pintype "bidirectional"))
    )
    (net (code "78") (name "Net-(R29-PadP$1)") (class "Default")
      (node (ref "R29") (pin "P$1") (pinfunction "P$1_P$1") (pintype "bidirectional"))
      (node (ref "VR29") (pin "P$1") (pinfunction "P$1_P$1") (pintype "bidirectional"))
      (node (ref "VR29") (pin "P$2") (pinfunction "P$2_P$2") (pintype "bidirectional"))
    )
    (net (code "79") (name "Net-(R30-PadP$1)") (class "Default")
      (node (ref "R30") (pin "P$1") (pinfunction "P$1_P$1") (pintype "bidirectional"))
      (node (ref "VR30") (pin "P$1") (pinfunction "P$1_P$1") (pintype "bidirectional"))
      (node (ref "VR30") (pin "P$2") (pinfunction "P$2_P$2") (pintype "bidirectional"))
    )
    (net (code "80") (name "Net-(R31-PadP$1)") (class "Default")
      (node (ref "R31") (pin "P$1") (pinfunction "P$1_P$1") (pintype "bidirectional"))
      (node (ref "VR31") (pin "P$1") (pinfunction "P$1_P$1") (pintype "bidirectional"))
      (node (ref "VR31") (pin "P$2") (pinfunction "P$2_P$2") (pintype "bidirectional"))
    )
    (net (code "81") (name "Net-(U$175-2)") (class "Default")
      (node (ref "U$175") (pin "P$2") (pinfunction "2_P$2") (pintype "bidirectional"))
      (node (ref "U$6") (pin "P$4") (pinfunction "P$4_P$4") (pintype "bidirectional"))
    )
    (net (code "82") (name "Net-(U$177-1)") (class "Default")
      (node (ref "U$177") (pin "P$1") (pinfunction "1_P$1") (pintype "bidirectional"))
      (node (ref "U2") (pin "20") (pinfunction "AREF_20") (pintype "input"))
    )
    (net (code "83") (name "Net-(U$315-DIN)") (class "Default")
      (node (ref "U$315") (pin "P$4") (pinfunction "DIN_P$4") (pintype "bidirectional"))
      (node (ref "U$316") (pin "P$2") (pinfunction "DOUT_P$2") (pintype "bidirectional"))
    )
    (net (code "84") (name "Net-(U$316-DIN)") (class "Default")
      (node (ref "U$316") (pin "P$4") (pinfunction "DIN_P$4") (pintype "bidirectional"))
      (node (ref "U$317") (pin "P$2") (pinfunction "DOUT_P$2") (pintype "bidirectional"))
    )
    (net (code "85") (name "Net-(U$317-DIN)") (class "Default")
      (node (ref "U$317") (pin "P$4") (pinfunction "DIN_P$4") (pintype "bidirectional"))
      (node (ref "U$318") (pin "P$2") (pinfunction "DOUT_P$2") (pintype "bidirectional"))
    )
    (net (code "86") (name "Net-(U$318-DIN)") (class "Default")
      (node (ref "U$318") (pin "P$4") (pinfunction "DIN_P$4") (pintype "bidirectional"))
      (node (ref "U$319") (pin "P$2") (pinfunction "DOUT_P$2") (pintype "bidirectional"))
    )
    (net (code "87") (name "Net-(U$319-DIN)") (class "Default")
      (node (ref "U$319") (pin "P$4") (pinfunction "DIN_P$4") (pintype "bidirectional"))
      (node (ref "U$320") (pin "P$2") (pinfunction "DOUT_P$2") (pintype "bidirectional"))
    )
    (net (code "88") (name "Net-(U$320-DIN)") (class "Default")
      (node (ref "U$320") (pin "P$4") (pinfunction "DIN_P$4") (pintype "bidirectional"))
      (node (ref "U$321") (pin "P$2") (pinfunction "DOUT_P$2") (pintype "bidirectional"))
    )
    (net (code "89") (name "Net-(U$321-DIN)") (class "Default")
      (node (ref "U$321") (pin "P$4") (pinfunction "DIN_P$4") (pintype "bidirectional"))
      (node (ref "U$322") (pin "P$2") (pinfunction "DOUT_P$2") (pintype "bidirectional"))
    )
    (net (code "90") (name "Net-(U$322-DIN)") (class "Default")
      (node (ref "U$322") (pin "P$4") (pinfunction "DIN_P$4") (pintype "bidirectional"))
      (node (ref "U$323") (pin "P$2") (pinfunction "DOUT_P$2") (pintype "bidirectional"))
    )
    (net (code "91") (name "Net-(U$323-DIN)") (class "Default")
      (node (ref "U$323") (pin "P$4") (pinfunction "DIN_P$4") (pintype "bidirectional"))
      (node (ref "U$324") (pin "P$2") (pinfunction "DOUT_P$2") (pintype "bidirectional"))
    )
    (net (code "92") (name "Net-(U$324-DIN)") (class "Default")
      (node (ref "U$324") (pin "P$4") (pinfunction "DIN_P$4") (pintype "bidirectional"))
      (node (ref "U$325") (pin "P$2") (pinfunction "DOUT_P$2") (pintype "bidirectional"))
    )
    (net (code "93") (name "Net-(U$325-DIN)") (class "Default")
      (node (ref "U$325") (pin "P$4") (pinfunction "DIN_P$4") (pintype "bidirectional"))
      (node (ref "U$326") (pin "P$2") (pinfunction "DOUT_P$2") (pintype "bidirectional"))
    )
    (net (code "94") (name "Net-(U$326-DIN)") (class "Default")
      (node (ref "U$326") (pin "P$4") (pinfunction "DIN_P$4") (pintype "bidirectional"))
      (node (ref "U$327") (pin "P$2") (pinfunction "DOUT_P$2") (pintype "bidirectional"))
    )
    (net (code "95") (name "Net-(U$327-DIN)") (class "Default")
      (node (ref "U$327") (pin "P$4") (pinfunction "DIN_P$4") (pintype "bidirectional"))
      (node (ref "U$328") (pin "P$2") (pinfunction "DOUT_P$2") (pintype "bidirectional"))
    )
    (net (code "96") (name "Net-(U$328-DIN)") (class "Default")
      (node (ref "U$328") (pin "P$4") (pinfunction "DIN_P$4") (pintype "bidirectional"))
      (node (ref "U$329") (pin "P$2") (pinfunction "DOUT_P$2") (pintype "bidirectional"))
    )
    (net (code "97") (name "Net-(U$329-DIN)") (class "Default")
      (node (ref "U$329") (pin "P$4") (pinfunction "DIN_P$4") (pintype "bidirectional"))
      (node (ref "U$330") (pin "P$2") (pinfunction "DOUT_P$2") (pintype "bidirectional"))
    )
    (net (code "98") (name "Net-(U$330-DIN)") (class "Default")
      (node (ref "U$330") (pin "P$4") (pinfunction "DIN_P$4") (pintype "bidirectional"))
      (node (ref "U$331") (pin "P$2") (pinfunction "DOUT_P$2") (pintype "bidirectional"))
    )
    (net (code "99") (name "Net-(U$331-DIN)") (class "Default")
      (node (ref "U$331") (pin "P$4") (pinfunction "DIN_P$4") (pintype "bidirectional"))
      (node (ref "U$332") (pin "P$2") (pinfunction "DOUT_P$2") (pintype "bidirectional"))
    )
    (net (code "100") (name "Net-(U$332-DIN)") (class "Default")
      (node (ref "U$332") (pin "P$4") (pinfunction "DIN_P$4") (pintype "bidirectional"))
      (node (ref "U$333") (pin "P$2") (pinfunction "DOUT_P$2") (pintype "bidirectional"))
    )
    (net (code "101") (name "Net-(U$333-DIN)") (class "Default")
      (node (ref "U$333") (pin "P$4") (pinfunction "DIN_P$4") (pintype "bidirectional"))
      (node (ref "U$334") (pin "P$2") (pinfunction "DOUT_P$2") (pintype "bidirectional"))
    )
    (net (code "102") (name "Net-(U$334-DIN)") (class "Default")
      (node (ref "U$334") (pin "P$4") (pinfunction "DIN_P$4") (pintype "bidirectional"))
      (node (ref "U$335") (pin "P$2") (pinfunction "DOUT_P$2") (pintype "bidirectional"))
    )
    (net (code "103") (name "Net-(U$335-DIN)") (class "Default")
      (node (ref "U$335") (pin "P$4") (pinfunction "DIN_P$4") (pintype "bidirectional"))
      (node (ref "U$336") (pin "P$2") (pinfunction "DOUT_P$2") (pintype "bidirectional"))
    )
    (net (code "104") (name "Net-(U$336-DIN)") (class "Default")
      (node (ref "U$336") (pin "P$4") (pinfunction "DIN_P$4") (pintype "bidirectional"))
      (node (ref "U$337") (pin "P$2") (pinfunction "DOUT_P$2") (pintype "bidirectional"))
    )
    (net (code "105") (name "Net-(U$337-DIN)") (class "Default")
      (node (ref "U$337") (pin "P$4") (pinfunction "DIN_P$4") (pintype "bidirectional"))
      (node (ref "U$338") (pin "P$2") (pinfunction "DOUT_P$2") (pintype "bidirectional"))
    )
    (net (code "106") (name "Net-(U$338-DIN)") (class "Default")
      (node (ref "U$338") (pin "P$4") (pinfunction "DIN_P$4") (pintype "bidirectional"))
      (node (ref "U$339") (pin "P$2") (pinfunction "DOUT_P$2") (pintype "bidirectional"))
    )
    (net (code "107") (name "Net-(U$339-DIN)") (class "Default")
      (node (ref "U$339") (pin "P$4") (pinfunction "DIN_P$4") (pintype "bidirectional"))
      (node (ref "U$340") (pin "P$2") (pinfunction "DOUT_P$2") (pintype "bidirectional"))
    )
    (net (code "108") (name "Net-(U$340-DIN)") (class "Default")
      (node (ref "U$340") (pin "P$4") (pinfunction "DIN_P$4") (pintype "bidirectional"))
      (node (ref "U$341") (pin "P$2") (pinfunction "DOUT_P$2") (pintype "bidirectional"))
    )
    (net (code "109") (name "Net-(U$341-DIN)") (class "Default")
      (node (ref "U$341") (pin "P$4") (pinfunction "DIN_P$4") (pintype "bidirectional"))
      (node (ref "U$342") (pin "P$2") (pinfunction "DOUT_P$2") (pintype "bidirectional"))
    )
    (net (code "110") (name "Net-(U$342-DIN)") (class "Default")
      (node (ref "U$342") (pin "P$4") (pinfunction "DIN_P$4") (pintype "bidirectional"))
      (node (ref "U$343") (pin "P$2") (pinfunction "DOUT_P$2") (pintype "bidirectional"))
    )
    (net (code "111") (name "Net-(U$343-DIN)") (class "Default")
      (node (ref "U$343") (pin "P$4") (pinfunction "DIN_P$4") (pintype "bidirectional"))
      (node (ref "U$344") (pin "P$2") (pinfunction "DOUT_P$2") (pintype "bidirectional"))
    )
    (net (code "112") (name "Net-(U$344-DIN)") (class "Default")
      (node (ref "U$344") (pin "P$4") (pinfunction "DIN_P$4") (pintype "bidirectional"))
      (node (ref "U$345") (pin "P$2") (pinfunction "DOUT_P$2") (pintype "bidirectional"))
    )
    (net (code "113") (name "Net-(U$345-DIN)") (class "Default")
      (node (ref "U$345") (pin "P$4") (pinfunction "DIN_P$4") (pintype "bidirectional"))
      (node (ref "U$346") (pin "P$2") (pinfunction "DOUT_P$2") (pintype "bidirectional"))
    )
    (net (code "114") (name "Net-(U2-PB6)") (class "Default")
      (node (ref "U2") (pin "7") (pinfunction "PB6_7") (pintype "bidirectional"))
      (node (ref "Y2") (pin "1") (pinfunction "IN_1") (pintype "input"))
    )
    (net (code "115") (name "Net-(U2-PB7)") (class "Default")
      (node (ref "U2") (pin "8") (pinfunction "PB7_8") (pintype "bidirectional"))
      (node (ref "Y2") (pin "3") (pinfunction "OUT_3") (pintype "output"))
    )
    (net (code "116") (name "Net-(U2-PD0)") (class "Default")
      (node (ref "U$6") (pin "P$3") (pinfunction "P$3_P$3") (pintype "bidirectional"))
      (node (ref "U2") (pin "30") (pinfunction "PD0_30") (pintype "bidirectional"))
    )
    (net (code "117") (name "Net-(U2-PD1)") (class "Default")
      (node (ref "U$6") (pin "P$2") (pinfunction "P$2_P$2") (pintype "bidirectional"))
      (node (ref "U2") (pin "31") (pinfunction "PD1_31") (pintype "bidirectional"))
    )
    (net (code "118") (name "RES") (class "Default")
      (node (ref "S2") (pin "1") (pinfunction "1_1") (pintype "bidirectional"))
      (node (ref "S2") (pin "2") (pinfunction "2_2") (pintype "bidirectional"))
      (node (ref "U$174") (pin "P$1") (pinfunction "P$1_P$1") (pintype "bidirectional"))
      (node (ref "U$175") (pin "P$1") (pinfunction "1_P$1") (pintype "bidirectional"))
      (node (ref "U$5") (pin "P$7") (pinfunction "RES_P$7") (pintype "bidirectional"))
      (node (ref "U2") (pin "29") (pinfunction "PC6/~{RESET}_29") (pintype "bidirectional"))
    )
    (net (code "119") (name "SCK") (class "Default")
      (node (ref "U$5") (pin "P$6") (pinfunction "SCK_P$6") (pintype "bidirectional"))
      (node (ref "U2") (pin "17") (pinfunction "PB5_17") (pintype "bidirectional"))
    )
    (net (code "120") (name "SS") (class "Default")
      (node (ref "U$5") (pin "P$3") (pinfunction "SS_P$3") (pintype "bidirectional"))
      (node (ref "U2") (pin "14") (pinfunction "PB2_14") (pintype "bidirectional"))
    )
    (net (code "121") (name "unconnected-(U$315-DOUT-PadP$2)") (class "Default")
      (node (ref "U$315") (pin "P$2") (pinfunction "DOUT_P$2") (pintype "bidirectional"))
    )
    (net (code "122") (name "unconnected-(U2-ADC6-Pad19)") (class "Default")
      (node (ref "U2") (pin "19") (pinfunction "ADC6_19") (pintype "bidirectional"))
    )
    (net (code "123") (name "unconnected-(U2-ADC7-Pad22)") (class "Default")
      (node (ref "U2") (pin "22") (pinfunction "ADC7_22") (pintype "bidirectional"))
    )
    (net (code "124") (name "unconnected-(U2-PB0-Pad12)") (class "Default")
      (node (ref "U2") (pin "12") (pinfunction "PB0_12") (pintype "bidirectional"))
    )
    (net (code "125") (name "unconnected-(U2-PB1-Pad13)") (class "Default")
      (node (ref "U2") (pin "13") (pinfunction "PB1_13") (pintype "bidirectional"))
    )
    (net (code "126") (name "unconnected-(U2-PC4-Pad27)") (class "Default")
      (node (ref "U2") (pin "27") (pinfunction "PC4_27") (pintype "bidirectional"))
    )
    (net (code "127") (name "unconnected-(U2-PC5-Pad28)") (class "Default")
      (node (ref "U2") (pin "28") (pinfunction "PC5_28") (pintype "bidirectional"))
    )
    (net (code "128") (name "unconnected-(U2-PD6-Pad10)") (class "Default")
      (node (ref "U2") (pin "10") (pinfunction "PD6_10") (pintype "bidirectional"))
    )
    (net (code "129") (name "unconnected-(U2-PD7-Pad11)") (class "Default")
      (node (ref "U2") (pin "11") (pinfunction "PD7_11") (pintype "bidirectional"))
    )
  )
)
